# keyBoard_B.net
KiCad netlist of a schematic drawn in EAGLE
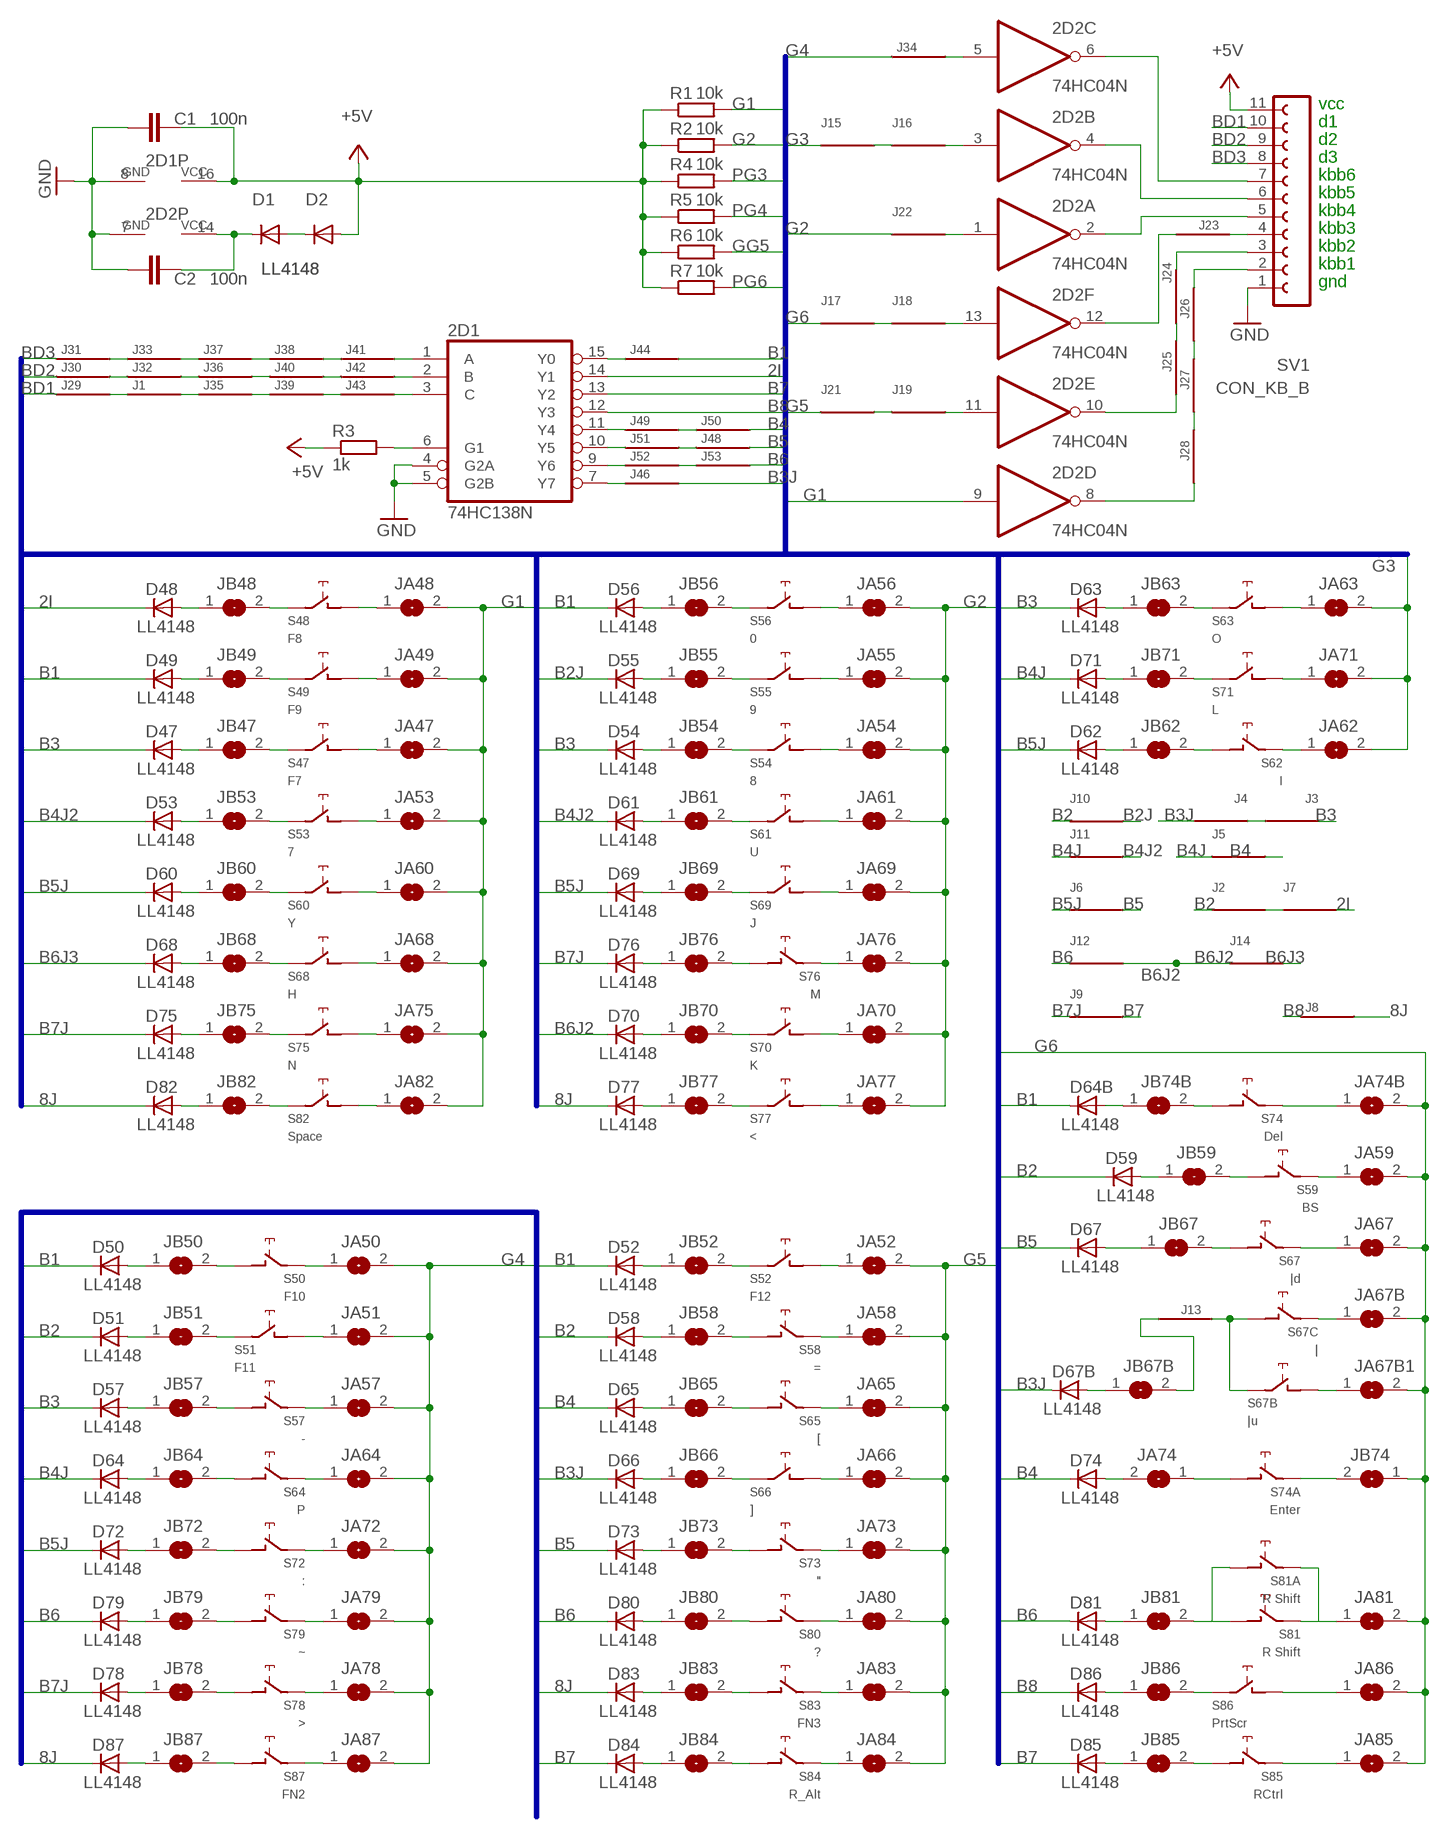
[diagram p0: schematic, sheet 1]

(export (version "E")
  (design (tool "Eeschema 10.0.6"))
  (components
    (comp (ref "2D1")
      (value "74HC138N")
      (footprint "eagle-import:DIL16")
      (libsource (lib "eagle-import") (part "74138NAC"))
    )
    (comp (ref "2D2")
      (value "74HC04N")
      (footprint "eagle-import:DIL14")
      (libsource (lib "eagle-import") (part "7404NALS"))
    )
    (comp (ref "C1")
      (value "100n")
      (footprint "eagle-import:C0805")
      (libsource (lib "eagle-import") (part "C-EUC0805"))
    )
    (comp (ref "C2")
      (value "100n")
      (footprint "eagle-import:C1206")
      (libsource (lib "eagle-import") (part "C-EUC1206"))
    )
    (comp (ref "D1")
      (value "LL4148")
      (footprint "eagle-import:SOD80C")
      (libsource (lib "eagle-import") (part "LL4148"))
    )
    (comp (ref "D2")
      (value "LL4148")
      (footprint "eagle-import:SOD80C")
      (libsource (lib "eagle-import") (part "LL4148"))
    )
    (comp (ref "D47")
      (value "LL4148")
      (footprint "eagle-import:SOD80C")
      (libsource (lib "eagle-import") (part "LL4148"))
    )
    (comp (ref "D48")
      (value "LL4148")
      (footprint "eagle-import:SOD80C")
      (libsource (lib "eagle-import") (part "LL4148"))
    )
    (comp (ref "D49")
      (value "LL4148")
      (footprint "eagle-import:SOD80C")
      (libsource (lib "eagle-import") (part "LL4148"))
    )
    (comp (ref "D50")
      (value "LL4148")
      (footprint "eagle-import:SOD80C")
      (libsource (lib "eagle-import") (part "LL4148"))
    )
    (comp (ref "D51")
      (value "LL4148")
      (footprint "eagle-import:SOD80C")
      (libsource (lib "eagle-import") (part "LL4148"))
    )
    (comp (ref "D52")
      (value "LL4148")
      (footprint "eagle-import:SOD80C")
      (libsource (lib "eagle-import") (part "LL4148"))
    )
    (comp (ref "D53")
      (value "LL4148")
      (footprint "eagle-import:SOD80C")
      (libsource (lib "eagle-import") (part "LL4148"))
    )
    (comp (ref "D54")
      (value "LL4148")
      (footprint "eagle-import:SOD80C")
      (libsource (lib "eagle-import") (part "LL4148"))
    )
    (comp (ref "D55")
      (value "LL4148")
      (footprint "eagle-import:SOD80C")
      (libsource (lib "eagle-import") (part "LL4148"))
    )
    (comp (ref "D56")
      (value "LL4148")
      (footprint "eagle-import:SOD80C")
      (libsource (lib "eagle-import") (part "LL4148"))
    )
    (comp (ref "D57")
      (value "LL4148")
      (footprint "eagle-import:SOD80C")
      (libsource (lib "eagle-import") (part "LL4148"))
    )
    (comp (ref "D58")
      (value "LL4148")
      (footprint "eagle-import:SOD80C")
      (libsource (lib "eagle-import") (part "LL4148"))
    )
    (comp (ref "D59")
      (value "LL4148")
      (footprint "eagle-import:SOD80C")
      (libsource (lib "eagle-import") (part "LL4148"))
    )
    (comp (ref "D60")
      (value "LL4148")
      (footprint "eagle-import:SOD80C")
      (libsource (lib "eagle-import") (part "LL4148"))
    )
    (comp (ref "D61")
      (value "LL4148")
      (footprint "eagle-import:SOD80C")
      (libsource (lib "eagle-import") (part "LL4148"))
    )
    (comp (ref "D62")
      (value "LL4148")
      (footprint "eagle-import:SOD80C")
      (libsource (lib "eagle-import") (part "LL4148"))
    )
    (comp (ref "D63")
      (value "LL4148")
      (footprint "eagle-import:SOD80C")
      (libsource (lib "eagle-import") (part "LL4148"))
    )
    (comp (ref "D64")
      (value "LL4148")
      (footprint "eagle-import:SOD80C")
      (libsource (lib "eagle-import") (part "LL4148"))
    )
    (comp (ref "D64B")
      (value "LL4148")
      (footprint "eagle-import:SOD80C")
      (libsource (lib "eagle-import") (part "LL4148"))
    )
    (comp (ref "D65")
      (value "LL4148")
      (footprint "eagle-import:SOD80C")
      (libsource (lib "eagle-import") (part "LL4148"))
    )
    (comp (ref "D66")
      (value "LL4148")
      (footprint "eagle-import:SOD80C")
      (libsource (lib "eagle-import") (part "LL4148"))
    )
    (comp (ref "D67")
      (value "LL4148")
      (footprint "eagle-import:SOD80C")
      (libsource (lib "eagle-import") (part "LL4148"))
    )
    (comp (ref "D67B")
      (value "LL4148")
      (footprint "eagle-import:SOD80C")
      (libsource (lib "eagle-import") (part "LL4148"))
    )
    (comp (ref "D68")
      (value "LL4148")
      (footprint "eagle-import:SOD80C")
      (libsource (lib "eagle-import") (part "LL4148"))
    )
    (comp (ref "D69")
      (value "LL4148")
      (footprint "eagle-import:SOD80C")
      (libsource (lib "eagle-import") (part "LL4148"))
    )
    (comp (ref "D70")
      (value "LL4148")
      (footprint "eagle-import:SOD80C")
      (libsource (lib "eagle-import") (part "LL4148"))
    )
    (comp (ref "D71")
      (value "LL4148")
      (footprint "eagle-import:SOD80C")
      (libsource (lib "eagle-import") (part "LL4148"))
    )
    (comp (ref "D72")
      (value "LL4148")
      (footprint "eagle-import:SOD80C")
      (libsource (lib "eagle-import") (part "LL4148"))
    )
    (comp (ref "D73")
      (value "LL4148")
      (footprint "eagle-import:SOD80C")
      (libsource (lib "eagle-import") (part "LL4148"))
    )
    (comp (ref "D74")
      (value "LL4148")
      (footprint "eagle-import:SOD80C")
      (libsource (lib "eagle-import") (part "LL4148"))
    )
    (comp (ref "D75")
      (value "LL4148")
      (footprint "eagle-import:SOD80C")
      (libsource (lib "eagle-import") (part "LL4148"))
    )
    (comp (ref "D76")
      (value "LL4148")
      (footprint "eagle-import:SOD80C")
      (libsource (lib "eagle-import") (part "LL4148"))
    )
    (comp (ref "D77")
      (value "LL4148")
      (footprint "eagle-import:SOD80C")
      (libsource (lib "eagle-import") (part "LL4148"))
    )
    (comp (ref "D78")
      (value "LL4148")
      (footprint "eagle-import:SOD80C")
      (libsource (lib "eagle-import") (part "LL4148"))
    )
    (comp (ref "D79")
      (value "LL4148")
      (footprint "eagle-import:SOD80C")
      (libsource (lib "eagle-import") (part "LL4148"))
    )
    (comp (ref "D80")
      (value "LL4148")
      (footprint "eagle-import:SOD80C")
      (libsource (lib "eagle-import") (part "LL4148"))
    )
    (comp (ref "D81")
      (value "LL4148")
      (footprint "eagle-import:SOD80C")
      (libsource (lib "eagle-import") (part "LL4148"))
    )
    (comp (ref "D82")
      (value "LL4148")
      (footprint "eagle-import:SOD80C")
      (libsource (lib "eagle-import") (part "LL4148"))
    )
    (comp (ref "D83")
      (value "LL4148")
      (footprint "eagle-import:SOD80C")
      (libsource (lib "eagle-import") (part "LL4148"))
    )
    (comp (ref "D84")
      (value "LL4148")
      (footprint "eagle-import:SOD80C")
      (libsource (lib "eagle-import") (part "LL4148"))
    )
    (comp (ref "D85")
      (value "LL4148")
      (footprint "eagle-import:SOD80C")
      (libsource (lib "eagle-import") (part "LL4148"))
    )
    (comp (ref "D86")
      (value "LL4148")
      (footprint "eagle-import:SOD80C")
      (libsource (lib "eagle-import") (part "LL4148"))
    )
    (comp (ref "D87")
      (value "LL4148")
      (footprint "eagle-import:SOD80C")
      (libsource (lib "eagle-import") (part "LL4148"))
    )
    (comp (ref "J1")
      (value "J")
      (footprint "eagle-import:R1206W")
      (libsource (lib "eagle-import") (part "J"))
    )
    (comp (ref "J2")
      (value "J")
      (footprint "eagle-import:R1206W")
      (libsource (lib "eagle-import") (part "J"))
    )
    (comp (ref "J3")
      (value "J")
      (footprint "eagle-import:R1206W")
      (libsource (lib "eagle-import") (part "J"))
    )
    (comp (ref "J4")
      (value "J")
      (footprint "eagle-import:R1206W")
      (libsource (lib "eagle-import") (part "J"))
    )
    (comp (ref "J5")
      (value "J")
      (footprint "eagle-import:R1206W")
      (libsource (lib "eagle-import") (part "J"))
    )
    (comp (ref "J6")
      (value "J")
      (footprint "eagle-import:R1206W")
      (libsource (lib "eagle-import") (part "J"))
    )
    (comp (ref "J7")
      (value "J")
      (footprint "eagle-import:R1206W")
      (libsource (lib "eagle-import") (part "J"))
    )
    (comp (ref "J8")
      (value "J")
      (footprint "eagle-import:R1206W")
      (libsource (lib "eagle-import") (part "J"))
    )
    (comp (ref "J9")
      (value "J")
      (footprint "eagle-import:R1206W")
      (libsource (lib "eagle-import") (part "J"))
    )
    (comp (ref "J10")
      (value "J")
      (footprint "eagle-import:R1206W")
      (libsource (lib "eagle-import") (part "J"))
    )
    (comp (ref "J11")
      (value "J")
      (footprint "eagle-import:R1206W")
      (libsource (lib "eagle-import") (part "J"))
    )
    (comp (ref "J12")
      (value "J")
      (footprint "eagle-import:R1206W")
      (libsource (lib "eagle-import") (part "J"))
    )
    (comp (ref "J13")
      (value "J")
      (footprint "eagle-import:R1206W")
      (libsource (lib "eagle-import") (part "J"))
    )
    (comp (ref "J14")
      (value "J")
      (footprint "eagle-import:R1206W")
      (libsource (lib "eagle-import") (part "J"))
    )
    (comp (ref "J15")
      (value "J")
      (footprint "eagle-import:R1206W")
      (libsource (lib "eagle-import") (part "J"))
    )
    (comp (ref "J16")
      (value "J")
      (footprint "eagle-import:R1206W")
      (libsource (lib "eagle-import") (part "J"))
    )
    (comp (ref "J17")
      (value "J")
      (footprint "eagle-import:R1206W")
      (libsource (lib "eagle-import") (part "J"))
    )
    (comp (ref "J18")
      (value "J")
      (footprint "eagle-import:R1206W")
      (libsource (lib "eagle-import") (part "J"))
    )
    (comp (ref "J19")
      (value "J")
      (footprint "eagle-import:R1206W")
      (libsource (lib "eagle-import") (part "J"))
    )
    (comp (ref "J21")
      (value "J")
      (footprint "eagle-import:R1206W")
      (libsource (lib "eagle-import") (part "J"))
    )
    (comp (ref "J22")
      (value "J")
      (footprint "eagle-import:R1206W")
      (libsource (lib "eagle-import") (part "J"))
    )
    (comp (ref "J23")
      (value "J")
      (footprint "eagle-import:R1206W")
      (libsource (lib "eagle-import") (part "J"))
    )
    (comp (ref "J24")
      (value "J")
      (footprint "eagle-import:R1206W")
      (libsource (lib "eagle-import") (part "J"))
    )
    (comp (ref "J25")
      (value "J")
      (footprint "eagle-import:R1206W")
      (libsource (lib "eagle-import") (part "J"))
    )
    (comp (ref "J26")
      (value "J")
      (footprint "eagle-import:R1206W")
      (libsource (lib "eagle-import") (part "J"))
    )
    (comp (ref "J27")
      (value "J")
      (footprint "eagle-import:R1206W")
      (libsource (lib "eagle-import") (part "J"))
    )
    (comp (ref "J28")
      (value "J")
      (footprint "eagle-import:R1206W")
      (libsource (lib "eagle-import") (part "J"))
    )
    (comp (ref "J29")
      (value "J")
      (footprint "eagle-import:R1206W")
      (libsource (lib "eagle-import") (part "J"))
    )
    (comp (ref "J30")
      (value "J")
      (footprint "eagle-import:R1206W")
      (libsource (lib "eagle-import") (part "J"))
    )
    (comp (ref "J31")
      (value "J")
      (footprint "eagle-import:R1206W")
      (libsource (lib "eagle-import") (part "J"))
    )
    (comp (ref "J32")
      (value "J")
      (footprint "eagle-import:R1206W")
      (libsource (lib "eagle-import") (part "J"))
    )
    (comp (ref "J33")
      (value "J")
      (footprint "eagle-import:R1206W")
      (libsource (lib "eagle-import") (part "J"))
    )
    (comp (ref "J34")
      (value "J")
      (footprint "eagle-import:R1206W")
      (libsource (lib "eagle-import") (part "J"))
    )
    (comp (ref "J35")
      (value "J")
      (footprint "eagle-import:R1206W")
      (libsource (lib "eagle-import") (part "J"))
    )
    (comp (ref "J36")
      (value "J")
      (footprint "eagle-import:R1206W")
      (libsource (lib "eagle-import") (part "J"))
    )
    (comp (ref "J37")
      (value "J")
      (footprint "eagle-import:R1206W")
      (libsource (lib "eagle-import") (part "J"))
    )
    (comp (ref "J38")
      (value "J")
      (footprint "eagle-import:R1206W")
      (libsource (lib "eagle-import") (part "J"))
    )
    (comp (ref "J39")
      (value "J")
      (footprint "eagle-import:R1206W")
      (libsource (lib "eagle-import") (part "J"))
    )
    (comp (ref "J40")
      (value "J")
      (footprint "eagle-import:R1206W")
      (libsource (lib "eagle-import") (part "J"))
    )
    (comp (ref "J41")
      (value "J")
      (footprint "eagle-import:R1206W")
      (libsource (lib "eagle-import") (part "J"))
    )
    (comp (ref "J42")
      (value "J")
      (footprint "eagle-import:R1206W")
      (libsource (lib "eagle-import") (part "J"))
    )
    (comp (ref "J43")
      (value "J")
      (footprint "eagle-import:R1206W")
      (libsource (lib "eagle-import") (part "J"))
    )
    (comp (ref "J44")
      (value "J")
      (footprint "eagle-import:R1206W")
      (libsource (lib "eagle-import") (part "J"))
    )
    (comp (ref "J46")
      (value "J")
      (footprint "eagle-import:R1206W")
      (libsource (lib "eagle-import") (part "J"))
    )
    (comp (ref "J48")
      (value "J")
      (footprint "eagle-import:R1206W")
      (libsource (lib "eagle-import") (part "J"))
    )
    (comp (ref "J49")
      (value "J")
      (footprint "eagle-import:R1206W")
      (libsource (lib "eagle-import") (part "J"))
    )
    (comp (ref "J50")
      (value "J")
      (footprint "eagle-import:R1206W")
      (libsource (lib "eagle-import") (part "J"))
    )
    (comp (ref "J51")
      (value "J")
      (footprint "eagle-import:R1206W")
      (libsource (lib "eagle-import") (part "J"))
    )
    (comp (ref "J52")
      (value "J")
      (footprint "eagle-import:R1206W")
      (libsource (lib "eagle-import") (part "J"))
    )
    (comp (ref "J53")
      (value "J")
      (footprint "eagle-import:R1206W")
      (libsource (lib "eagle-import") (part "J"))
    )
    (comp (ref "JA47")
      (value "SJ")
      (footprint "eagle-import:SJ")
      (libsource (lib "eagle-import") (part "SJ"))
    )
    (comp (ref "JA48")
      (value "SJ")
      (footprint "eagle-import:SJ")
      (libsource (lib "eagle-import") (part "SJ"))
    )
    (comp (ref "JA49")
      (value "SJ")
      (footprint "eagle-import:SJ")
      (libsource (lib "eagle-import") (part "SJ"))
    )
    (comp (ref "JA50")
      (value "SJ")
      (footprint "eagle-import:SJ")
      (libsource (lib "eagle-import") (part "SJ"))
    )
    (comp (ref "JA51")
      (value "SJ")
      (footprint "eagle-import:SJ")
      (libsource (lib "eagle-import") (part "SJ"))
    )
    (comp (ref "JA52")
      (value "SJ")
      (footprint "eagle-import:SJ")
      (libsource (lib "eagle-import") (part "SJ"))
    )
    (comp (ref "JA53")
      (value "SJ")
      (footprint "eagle-import:SJ")
      (libsource (lib "eagle-import") (part "SJ"))
    )
    (comp (ref "JA54")
      (value "SJ")
      (footprint "eagle-import:SJ")
      (libsource (lib "eagle-import") (part "SJ"))
    )
    (comp (ref "JA55")
      (value "SJ")
      (footprint "eagle-import:SJ")
      (libsource (lib "eagle-import") (part "SJ"))
    )
    (comp (ref "JA56")
      (value "SJ")
      (footprint "eagle-import:SJ")
      (libsource (lib "eagle-import") (part "SJ"))
    )
    (comp (ref "JA57")
      (value "SJ")
      (footprint "eagle-import:SJ")
      (libsource (lib "eagle-import") (part "SJ"))
    )
    (comp (ref "JA58")
      (value "SJ")
      (footprint "eagle-import:SJ")
      (libsource (lib "eagle-import") (part "SJ"))
    )
    (comp (ref "JA59")
      (value "SJ")
      (footprint "eagle-import:SJ")
      (libsource (lib "eagle-import") (part "SJ"))
    )
    (comp (ref "JA60")
      (value "SJ")
      (footprint "eagle-import:SJ")
      (libsource (lib "eagle-import") (part "SJ"))
    )
    (comp (ref "JA61")
      (value "SJ")
      (footprint "eagle-import:SJ")
      (libsource (lib "eagle-import") (part "SJ"))
    )
    (comp (ref "JA62")
      (value "SJ")
      (footprint "eagle-import:SJ")
      (libsource (lib "eagle-import") (part "SJ"))
    )
    (comp (ref "JA63")
      (value "SJ")
      (footprint "eagle-import:SJ")
      (libsource (lib "eagle-import") (part "SJ"))
    )
    (comp (ref "JA64")
      (value "SJ")
      (footprint "eagle-import:SJ")
      (libsource (lib "eagle-import") (part "SJ"))
    )
    (comp (ref "JA65")
      (value "SJ")
      (footprint "eagle-import:SJ")
      (libsource (lib "eagle-import") (part "SJ"))
    )
    (comp (ref "JA66")
      (value "SJ")
      (footprint "eagle-import:SJ")
      (libsource (lib "eagle-import") (part "SJ"))
    )
    (comp (ref "JA67")
      (value "SJ")
      (footprint "eagle-import:SJ")
      (libsource (lib "eagle-import") (part "SJ"))
    )
    (comp (ref "JA67B")
      (value "SJ")
      (footprint "eagle-import:SJ")
      (libsource (lib "eagle-import") (part "SJ"))
    )
    (comp (ref "JA67B1")
      (value "SJ")
      (footprint "eagle-import:SJ")
      (libsource (lib "eagle-import") (part "SJ"))
    )
    (comp (ref "JA68")
      (value "SJ")
      (footprint "eagle-import:SJ")
      (libsource (lib "eagle-import") (part "SJ"))
    )
    (comp (ref "JA69")
      (value "SJ")
      (footprint "eagle-import:SJ")
      (libsource (lib "eagle-import") (part "SJ"))
    )
    (comp (ref "JA70")
      (value "SJ")
      (footprint "eagle-import:SJ")
      (libsource (lib "eagle-import") (part "SJ"))
    )
    (comp (ref "JA71")
      (value "SJ")
      (footprint "eagle-import:SJ")
      (libsource (lib "eagle-import") (part "SJ"))
    )
    (comp (ref "JA72")
      (value "SJ")
      (footprint "eagle-import:SJ")
      (libsource (lib "eagle-import") (part "SJ"))
    )
    (comp (ref "JA73")
      (value "SJ")
      (footprint "eagle-import:SJ")
      (libsource (lib "eagle-import") (part "SJ"))
    )
    (comp (ref "JA74")
      (value "SJ")
      (footprint "eagle-import:SJ")
      (libsource (lib "eagle-import") (part "SJ"))
    )
    (comp (ref "JA74B")
      (value "SJ")
      (footprint "eagle-import:SJ")
      (libsource (lib "eagle-import") (part "SJ"))
    )
    (comp (ref "JA75")
      (value "SJ")
      (footprint "eagle-import:SJ")
      (libsource (lib "eagle-import") (part "SJ"))
    )
    (comp (ref "JA76")
      (value "SJ")
      (footprint "eagle-import:SJ")
      (libsource (lib "eagle-import") (part "SJ"))
    )
    (comp (ref "JA77")
      (value "SJ")
      (footprint "eagle-import:SJ")
      (libsource (lib "eagle-import") (part "SJ"))
    )
    (comp (ref "JA78")
      (value "SJ")
      (footprint "eagle-import:SJ")
      (libsource (lib "eagle-import") (part "SJ"))
    )
    (comp (ref "JA79")
      (value "SJ")
      (footprint "eagle-import:SJ")
      (libsource (lib "eagle-import") (part "SJ"))
    )
    (comp (ref "JA80")
      (value "SJ")
      (footprint "eagle-import:SJ")
      (libsource (lib "eagle-import") (part "SJ"))
    )
    (comp (ref "JA81")
      (value "SJ")
      (footprint "eagle-import:SJ")
      (libsource (lib "eagle-import") (part "SJ"))
    )
    (comp (ref "JA82")
      (value "SJ")
      (footprint "eagle-import:SJ")
      (libsource (lib "eagle-import") (part "SJ"))
    )
    (comp (ref "JA83")
      (value "SJ")
      (footprint "eagle-import:SJ")
      (libsource (lib "eagle-import") (part "SJ"))
    )
    (comp (ref "JA84")
      (value "SJ")
      (footprint "eagle-import:SJ")
      (libsource (lib "eagle-import") (part "SJ"))
    )
    (comp (ref "JA85")
      (value "SJ")
      (footprint "eagle-import:SJ")
      (libsource (lib "eagle-import") (part "SJ"))
    )
    (comp (ref "JA86")
      (value "SJ")
      (footprint "eagle-import:SJ")
      (libsource (lib "eagle-import") (part "SJ"))
    )
    (comp (ref "JA87")
      (value "SJ")
      (footprint "eagle-import:SJ")
      (libsource (lib "eagle-import") (part "SJ"))
    )
    (comp (ref "JB47")
      (value "SJ")
      (footprint "eagle-import:SJ")
      (libsource (lib "eagle-import") (part "SJ"))
    )
    (comp (ref "JB48")
      (value "SJ")
      (footprint "eagle-import:SJ")
      (libsource (lib "eagle-import") (part "SJ"))
    )
    (comp (ref "JB49")
      (value "SJ")
      (footprint "eagle-import:SJ")
      (libsource (lib "eagle-import") (part "SJ"))
    )
    (comp (ref "JB50")
      (value "SJ")
      (footprint "eagle-import:SJ")
      (libsource (lib "eagle-import") (part "SJ"))
    )
    (comp (ref "JB51")
      (value "SJ")
      (footprint "eagle-import:SJ")
      (libsource (lib "eagle-import") (part "SJ"))
    )
    (comp (ref "JB52")
      (value "SJ")
      (footprint "eagle-import:SJ")
      (libsource (lib "eagle-import") (part "SJ"))
    )
    (comp (ref "JB53")
      (value "SJ")
      (footprint "eagle-import:SJ")
      (libsource (lib "eagle-import") (part "SJ"))
    )
    (comp (ref "JB54")
      (value "SJ")
      (footprint "eagle-import:SJ")
      (libsource (lib "eagle-import") (part "SJ"))
    )
    (comp (ref "JB55")
      (value "SJ")
      (footprint "eagle-import:SJ")
      (libsource (lib "eagle-import") (part "SJ"))
    )
    (comp (ref "JB56")
      (value "SJ")
      (footprint "eagle-import:SJ")
      (libsource (lib "eagle-import") (part "SJ"))
    )
    (comp (ref "JB57")
      (value "SJ")
      (footprint "eagle-import:SJ")
      (libsource (lib "eagle-import") (part "SJ"))
    )
    (comp (ref "JB58")
      (value "SJ")
      (footprint "eagle-import:SJ")
      (libsource (lib "eagle-import") (part "SJ"))
    )
    (comp (ref "JB59")
      (value "SJ")
      (footprint "eagle-import:SJ")
      (libsource (lib "eagle-import") (part "SJ"))
    )
    (comp (ref "JB60")
      (value "SJ")
      (footprint "eagle-import:SJ")
      (libsource (lib "eagle-import") (part "SJ"))
    )
    (comp (ref "JB61")
      (value "SJ")
      (footprint "eagle-import:SJ")
      (libsource (lib "eagle-import") (part "SJ"))
    )
    (comp (ref "JB62")
      (value "SJ")
      (footprint "eagle-import:SJ")
      (libsource (lib "eagle-import") (part "SJ"))
    )
    (comp (ref "JB63")
      (value "SJ")
      (footprint "eagle-import:SJ")
      (libsource (lib "eagle-import") (part "SJ"))
    )
    (comp (ref "JB64")
      (value "SJ")
      (footprint "eagle-import:SJ")
      (libsource (lib "eagle-import") (part "SJ"))
    )
    (comp (ref "JB65")
      (value "SJ")
      (footprint "eagle-import:SJ")
      (libsource (lib "eagle-import") (part "SJ"))
    )
    (comp (ref "JB66")
      (value "SJ")
      (footprint "eagle-import:SJ")
      (libsource (lib "eagle-import") (part "SJ"))
    )
    (comp (ref "JB67")
      (value "SJ")
      (footprint "eagle-import:SJ")
      (libsource (lib "eagle-import") (part "SJ"))
    )
    (comp (ref "JB67B")
      (value "SJ")
      (footprint "eagle-import:SJ")
      (libsource (lib "eagle-import") (part "SJ"))
    )
    (comp (ref "JB68")
      (value "SJ")
      (footprint "eagle-import:SJ")
      (libsource (lib "eagle-import") (part "SJ"))
    )
    (comp (ref "JB69")
      (value "SJ")
      (footprint "eagle-import:SJ")
      (libsource (lib "eagle-import") (part "SJ"))
    )
    (comp (ref "JB70")
      (value "SJ")
      (footprint "eagle-import:SJ")
      (libsource (lib "eagle-import") (part "SJ"))
    )
    (comp (ref "JB71")
      (value "SJ")
      (footprint "eagle-import:SJ")
      (libsource (lib "eagle-import") (part "SJ"))
    )
    (comp (ref "JB72")
      (value "SJ")
      (footprint "eagle-import:SJ")
      (libsource (lib "eagle-import") (part "SJ"))
    )
    (comp (ref "JB73")
      (value "SJ")
      (footprint "eagle-import:SJ")
      (libsource (lib "eagle-import") (part "SJ"))
    )
    (comp (ref "JB74")
      (value "SJ")
      (footprint "eagle-import:SJ")
      (libsource (lib "eagle-import") (part "SJ"))
    )
    (comp (ref "JB74B")
      (value "SJ")
      (footprint "eagle-import:SJ")
      (libsource (lib "eagle-import") (part "SJ"))
    )
    (comp (ref "JB75")
      (value "SJ")
      (footprint "eagle-import:SJ")
      (libsource (lib "eagle-import") (part "SJ"))
    )
    (comp (ref "JB76")
      (value "SJ")
      (footprint "eagle-import:SJ")
      (libsource (lib "eagle-import") (part "SJ"))
    )
    (comp (ref "JB77")
      (value "SJ")
      (footprint "eagle-import:SJ")
      (libsource (lib "eagle-import") (part "SJ"))
    )
    (comp (ref "JB78")
      (value "SJ")
      (footprint "eagle-import:SJ")
      (libsource (lib "eagle-import") (part "SJ"))
    )
    (comp (ref "JB79")
      (value "SJ")
      (footprint "eagle-import:SJ")
      (libsource (lib "eagle-import") (part "SJ"))
    )
    (comp (ref "JB80")
      (value "SJ")
      (footprint "eagle-import:SJ")
      (libsource (lib "eagle-import") (part "SJ"))
    )
    (comp (ref "JB81")
      (value "SJ")
      (footprint "eagle-import:SJ")
      (libsource (lib "eagle-import") (part "SJ"))
    )
    (comp (ref "JB82")
      (value "SJ")
      (footprint "eagle-import:SJ")
      (libsource (lib "eagle-import") (part "SJ"))
    )
    (comp (ref "JB83")
      (value "SJ")
      (footprint "eagle-import:SJ")
      (libsource (lib "eagle-import") (part "SJ"))
    )
    (comp (ref "JB84")
      (value "SJ")
      (footprint "eagle-import:SJ")
      (libsource (lib "eagle-import") (part "SJ"))
    )
    (comp (ref "JB85")
      (value "SJ")
      (footprint "eagle-import:SJ")
      (libsource (lib "eagle-import") (part "SJ"))
    )
    (comp (ref "JB86")
      (value "SJ")
      (footprint "eagle-import:SJ")
      (libsource (lib "eagle-import") (part "SJ"))
    )
    (comp (ref "JB87")
      (value "SJ")
      (footprint "eagle-import:SJ")
      (libsource (lib "eagle-import") (part "SJ"))
    )
    (comp (ref "R1")
      (value "10k")
      (footprint "eagle-import:R0805")
      (libsource (lib "eagle-import") (part "R-EU_R0805"))
    )
    (comp (ref "R2")
      (value "10k")
      (footprint "eagle-import:R0805")
      (libsource (lib "eagle-import") (part "R-EU_R0805"))
    )
    (comp (ref "R3")
      (value "1k")
      (footprint "eagle-import:R0805")
      (libsource (lib "eagle-import") (part "R-EU_R0805"))
    )
    (comp (ref "R4")
      (value "10k")
      (footprint "eagle-import:R0805")
      (libsource (lib "eagle-import") (part "R-EU_R0805"))
    )
    (comp (ref "R5")
      (value "10k")
      (footprint "eagle-import:R1206W")
      (libsource (lib "eagle-import") (part "R-EU_R1206W"))
    )
    (comp (ref "R6")
      (value "10k")
      (footprint "eagle-import:R0805")
      (libsource (lib "eagle-import") (part "R-EU_R0805"))
    )
    (comp (ref "R7")
      (value "10k")
      (footprint "eagle-import:R0805")
      (libsource (lib "eagle-import") (part "R-EU_R0805"))
    )
    (comp (ref "S47")
      (value "F7")
      (footprint "eagle-import:CHERRY-MX-4P")
      (libsource (lib "eagle-import") (part "CHERRY-MX-4P"))
    )
    (comp (ref "S48")
      (value "F8")
      (footprint "eagle-import:CHERRY-MX-4P")
      (libsource (lib "eagle-import") (part "CHERRY-MX-4P"))
    )
    (comp (ref "S49")
      (value "F9")
      (footprint "eagle-import:CHERRY-MX-4P")
      (libsource (lib "eagle-import") (part "CHERRY-MX-4P"))
    )
    (comp (ref "S50")
      (value "F10")
      (footprint "eagle-import:CHERRY-MX-4P")
      (libsource (lib "eagle-import") (part "CHERRY-MX-4P"))
    )
    (comp (ref "S51")
      (value "F11")
      (footprint "eagle-import:CHERRY-MX-4P")
      (libsource (lib "eagle-import") (part "CHERRY-MX-4P"))
    )
    (comp (ref "S52")
      (value "F12")
      (footprint "eagle-import:CHERRY-MX-4P")
      (libsource (lib "eagle-import") (part "CHERRY-MX-4P"))
    )
    (comp (ref "S53")
      (value "7")
      (footprint "eagle-import:CHERRY-MX-4P")
      (libsource (lib "eagle-import") (part "CHERRY-MX-4P"))
    )
    (comp (ref "S54")
      (value "8")
      (footprint "eagle-import:CHERRY-MX-4P")
      (libsource (lib "eagle-import") (part "CHERRY-MX-4P"))
    )
    (comp (ref "S55")
      (value "9")
      (footprint "eagle-import:CHERRY-MX-4P")
      (libsource (lib "eagle-import") (part "CHERRY-MX-4P"))
    )
    (comp (ref "S56")
      (value "0")
      (footprint "eagle-import:CHERRY-MX-4P")
      (libsource (lib "eagle-import") (part "CHERRY-MX-4P"))
    )
    (comp (ref "S57")
      (value "-")
      (footprint "eagle-import:CHERRY-MX-4P")
      (libsource (lib "eagle-import") (part "CHERRY-MX-4P"))
    )
    (comp (ref "S58")
      (value "=")
      (footprint "eagle-import:CHERRY-MX-4P")
      (libsource (lib "eagle-import") (part "CHERRY-MX-4P"))
    )
    (comp (ref "S59")
      (value "BS")
      (footprint "eagle-import:CHERRY-MX-4P")
      (libsource (lib "eagle-import") (part "CHERRY-MX-4P"))
    )
    (comp (ref "S60")
      (value "Y")
      (footprint "eagle-import:CHERRY-MX-4P")
      (libsource (lib "eagle-import") (part "CHERRY-MX-4P"))
    )
    (comp (ref "S61")
      (value "U")
      (footprint "eagle-import:CHERRY-MX-4P")
      (libsource (lib "eagle-import") (part "CHERRY-MX-4P"))
    )
    (comp (ref "S62")
      (value "I")
      (footprint "eagle-import:CHERRY-MX-4P")
      (libsource (lib "eagle-import") (part "CHERRY-MX-4P"))
    )
    (comp (ref "S63")
      (value "O")
      (footprint "eagle-import:CHERRY-MX-4P")
      (libsource (lib "eagle-import") (part "CHERRY-MX-4P"))
    )
    (comp (ref "S64")
      (value "P")
      (footprint "eagle-import:CHERRY-MX-4P")
      (libsource (lib "eagle-import") (part "CHERRY-MX-4P"))
    )
    (comp (ref "S65")
      (value "[")
      (footprint "eagle-import:CHERRY-MX-4P")
      (libsource (lib "eagle-import") (part "CHERRY-MX-4P"))
    )
    (comp (ref "S66")
      (value "]")
      (footprint "eagle-import:CHERRY-MX-4P")
      (libsource (lib "eagle-import") (part "CHERRY-MX-4P"))
    )
    (comp (ref "S67")
      (value "|d")
      (footprint "eagle-import:CHERRY-MX-4P")
      (libsource (lib "eagle-import") (part "CHERRY-MX-4P"))
    )
    (comp (ref "S67B")
      (value "|u")
      (footprint "eagle-import:CHERRY-MX")
      (libsource (lib "eagle-import") (part "CHERRY-MX"))
    )
    (comp (ref "S67C")
      (value "|")
      (footprint "eagle-import:CHERRY-MX-4P")
      (libsource (lib "eagle-import") (part "CHERRY-MX-4P"))
    )
    (comp (ref "S68")
      (value "H")
      (footprint "eagle-import:CHERRY-MX-4P")
      (libsource (lib "eagle-import") (part "CHERRY-MX-4P"))
    )
    (comp (ref "S69")
      (value "J")
      (footprint "eagle-import:CHERRY-MX-4P")
      (libsource (lib "eagle-import") (part "CHERRY-MX-4P"))
    )
    (comp (ref "S70")
      (value "K")
      (footprint "eagle-import:CHERRY-MX-4P")
      (libsource (lib "eagle-import") (part "CHERRY-MX-4P"))
    )
    (comp (ref "S71")
      (value "L")
      (footprint "eagle-import:CHERRY-MX-4P")
      (libsource (lib "eagle-import") (part "CHERRY-MX-4P"))
    )
    (comp (ref "S72")
      (value ":")
      (footprint "eagle-import:CHERRY-MX-4P")
      (libsource (lib "eagle-import") (part "CHERRY-MX-4P"))
    )
    (comp (ref "S73")
      (value "\"")
      (footprint "eagle-import:CHERRY-MX-4P")
      (libsource (lib "eagle-import") (part "CHERRY-MX-4P"))
    )
    (comp (ref "S74")
      (value "Del")
      (footprint "eagle-import:CHERRY-MX-4P")
      (libsource (lib "eagle-import") (part "CHERRY-MX-4P"))
    )
    (comp (ref "S74A")
      (value "Enter")
      (footprint "eagle-import:CHERRY-MX-4P")
      (libsource (lib "eagle-import") (part "CHERRY-MX-4P"))
    )
    (comp (ref "S75")
      (value "N")
      (footprint "eagle-import:CHERRY-MX-4P")
      (libsource (lib "eagle-import") (part "CHERRY-MX-4P"))
    )
    (comp (ref "S76")
      (value "M")
      (footprint "eagle-import:CHERRY-MX-4P")
      (libsource (lib "eagle-import") (part "CHERRY-MX-4P"))
    )
    (comp (ref "S77")
      (value "<")
      (footprint "eagle-import:CHERRY-MX-4P")
      (libsource (lib "eagle-import") (part "CHERRY-MX-4P"))
    )
    (comp (ref "S78")
      (value ">")
      (footprint "eagle-import:CHERRY-MX-4P")
      (libsource (lib "eagle-import") (part "CHERRY-MX-4P"))
    )
    (comp (ref "S79")
      (value "~")
      (footprint "eagle-import:CHERRY-MX-4P")
      (libsource (lib "eagle-import") (part "CHERRY-MX-4P"))
    )
    (comp (ref "S80")
      (value "?")
      (footprint "eagle-import:CHERRY-MX-4P")
      (libsource (lib "eagle-import") (part "CHERRY-MX-4P"))
    )
    (comp (ref "S81")
      (value "R Shift")
      (footprint "eagle-import:CHERRY-MX-4P")
      (libsource (lib "eagle-import") (part "CHERRY-MX-4P"))
    )
    (comp (ref "S81A")
      (value "R Shift")
      (footprint "eagle-import:CHERRY-MX-4P")
      (libsource (lib "eagle-import") (part "CHERRY-MX-4P"))
    )
    (comp (ref "S82")
      (value "Space")
      (footprint "eagle-import:CHERRY-MX-4P")
      (libsource (lib "eagle-import") (part "CHERRY-MX-4P"))
    )
    (comp (ref "S83")
      (value "FN3")
      (footprint "eagle-import:CHERRY-MX-4P")
      (libsource (lib "eagle-import") (part "CHERRY-MX-4P"))
    )
    (comp (ref "S84")
      (value "R_Alt")
      (footprint "eagle-import:CHERRY-MX-4P")
      (libsource (lib "eagle-import") (part "CHERRY-MX-4P"))
    )
    (comp (ref "S85")
      (value "RCtrl")
      (footprint "eagle-import:CHERRY-MX-4P")
      (libsource (lib "eagle-import") (part "CHERRY-MX-4P"))
    )
    (comp (ref "S86")
      (value "PrtScr")
      (footprint "eagle-import:CHERRY-MX-4P")
      (libsource (lib "eagle-import") (part "CHERRY-MX-4P"))
    )
    (comp (ref "S87")
      (value "FN2")
      (footprint "eagle-import:CHERRY-MX-4P")
      (libsource (lib "eagle-import") (part "CHERRY-MX-4P"))
    )
    (comp (ref "SV1")
      (value "CON_KB_B")
      (footprint "eagle-import:FE12")
      (libsource (lib "eagle-import") (part "FE12-1"))
    )
  )
  (nets
    (net (code "20") (name "+5V") (class "Default")
      (node (ref "2D1") (pin "16") (pinfunction "VCC_16") (pintype "power_in"))
      (node (ref "C1") (pin "1") (pinfunction "1_1") (pintype "passive"))
      (node (ref "D2") (pin "A") (pinfunction "A_A") (pintype "passive"))
      (node (ref "R1") (pin "1") (pinfunction "1_1") (pintype "passive"))
      (node (ref "R2") (pin "1") (pinfunction "1_1") (pintype "passive"))
      (node (ref "R3") (pin "1") (pinfunction "1_1") (pintype "passive"))
      (node (ref "R4") (pin "1") (pinfunction "1_1") (pintype "passive"))
      (node (ref "R5") (pin "1") (pinfunction "1_1") (pintype "passive"))
      (node (ref "R6") (pin "1") (pinfunction "1_1") (pintype "passive"))
      (node (ref "R7") (pin "1") (pinfunction "1_1") (pintype "passive"))
      (node (ref "SV1") (pin "11") (pinfunction "11_11") (pintype "passive"))
    )
    (net (code "21") (name "/2I") (class "Default")
      (node (ref "2D1") (pin "14") (pinfunction "Y1_14") (pintype "output"))
      (node (ref "D48") (pin "C") (pinfunction "C_C") (pintype "passive"))
      (node (ref "J7") (pin "1") (pinfunction "P$1_1") (pintype "bidirectional"))
    )
    (net (code "22") (name "/8J") (class "Default")
      (node (ref "D77") (pin "C") (pinfunction "C_C") (pintype "passive"))
      (node (ref "D82") (pin "C") (pinfunction "C_C") (pintype "passive"))
      (node (ref "D83") (pin "C") (pinfunction "C_C") (pintype "passive"))
      (node (ref "D87") (pin "C") (pinfunction "C_C") (pintype "passive"))
      (node (ref "J8") (pin "1") (pinfunction "P$1_1") (pintype "bidirectional"))
    )
    (net (code "23") (name "/B1") (class "Default")
      (node (ref "D49") (pin "C") (pinfunction "C_C") (pintype "passive"))
      (node (ref "D50") (pin "C") (pinfunction "C_C") (pintype "passive"))
      (node (ref "D52") (pin "C") (pinfunction "C_C") (pintype "passive"))
      (node (ref "D56") (pin "C") (pinfunction "C_C") (pintype "passive"))
      (node (ref "D64B") (pin "C") (pinfunction "C_C") (pintype "passive"))
      (node (ref "J44") (pin "1") (pinfunction "P$1_1") (pintype "bidirectional"))
    )
    (net (code "24") (name "/B2") (class "Default")
      (node (ref "D51") (pin "C") (pinfunction "C_C") (pintype "passive"))
      (node (ref "D58") (pin "C") (pinfunction "C_C") (pintype "passive"))
      (node (ref "D59") (pin "C") (pinfunction "C_C") (pintype "passive"))
      (node (ref "J10") (pin "2") (pinfunction "P$2_2") (pintype "bidirectional"))
      (node (ref "J2") (pin "2") (pinfunction "P$2_2") (pintype "bidirectional"))
    )
    (net (code "25") (name "/B2J") (class "Default")
      (node (ref "D55") (pin "C") (pinfunction "C_C") (pintype "passive"))
      (node (ref "J10") (pin "1") (pinfunction "P$1_1") (pintype "bidirectional"))
    )
    (net (code "26") (name "/B3") (class "Default")
      (node (ref "D47") (pin "C") (pinfunction "C_C") (pintype "passive"))
      (node (ref "D54") (pin "C") (pinfunction "C_C") (pintype "passive"))
      (node (ref "D57") (pin "C") (pinfunction "C_C") (pintype "passive"))
      (node (ref "D63") (pin "C") (pinfunction "C_C") (pintype "passive"))
      (node (ref "J3") (pin "2") (pinfunction "P$2_2") (pintype "bidirectional"))
    )
    (net (code "27") (name "/B3J") (class "Default")
      (node (ref "D66") (pin "C") (pinfunction "C_C") (pintype "passive"))
      (node (ref "D67B") (pin "C") (pinfunction "C_C") (pintype "passive"))
      (node (ref "J4") (pin "1") (pinfunction "P$1_1") (pintype "bidirectional"))
      (node (ref "J46") (pin "1") (pinfunction "P$1_1") (pintype "bidirectional"))
    )
    (net (code "28") (name "/B4") (class "Default")
      (node (ref "D65") (pin "C") (pinfunction "C_C") (pintype "passive"))
      (node (ref "D74") (pin "C") (pinfunction "C_C") (pintype "passive"))
      (node (ref "J5") (pin "1") (pinfunction "P$1_1") (pintype "bidirectional"))
      (node (ref "J50") (pin "1") (pinfunction "P$1_1") (pintype "bidirectional"))
    )
    (net (code "29") (name "/B4J") (class "Default")
      (node (ref "D64") (pin "C") (pinfunction "C_C") (pintype "passive"))
      (node (ref "D71") (pin "C") (pinfunction "C_C") (pintype "passive"))
      (node (ref "J11") (pin "2") (pinfunction "P$2_2") (pintype "bidirectional"))
      (node (ref "J5") (pin "2") (pinfunction "P$2_2") (pintype "bidirectional"))
    )
    (net (code "30") (name "/B4J2") (class "Default")
      (node (ref "D53") (pin "C") (pinfunction "C_C") (pintype "passive"))
      (node (ref "D61") (pin "C") (pinfunction "C_C") (pintype "passive"))
      (node (ref "J11") (pin "1") (pinfunction "P$1_1") (pintype "bidirectional"))
    )
    (net (code "31") (name "/B5") (class "Default")
      (node (ref "D67") (pin "C") (pinfunction "C_C") (pintype "passive"))
      (node (ref "D73") (pin "C") (pinfunction "C_C") (pintype "passive"))
      (node (ref "J48") (pin "1") (pinfunction "P$1_1") (pintype "bidirectional"))
      (node (ref "J6") (pin "1") (pinfunction "P$1_1") (pintype "bidirectional"))
    )
    (net (code "32") (name "/B5J") (class "Default")
      (node (ref "D60") (pin "C") (pinfunction "C_C") (pintype "passive"))
      (node (ref "D62") (pin "C") (pinfunction "C_C") (pintype "passive"))
      (node (ref "D69") (pin "C") (pinfunction "C_C") (pintype "passive"))
      (node (ref "D72") (pin "C") (pinfunction "C_C") (pintype "passive"))
      (node (ref "J6") (pin "2") (pinfunction "P$2_2") (pintype "bidirectional"))
    )
    (net (code "33") (name "/B6") (class "Default")
      (node (ref "D79") (pin "C") (pinfunction "C_C") (pintype "passive"))
      (node (ref "D80") (pin "C") (pinfunction "C_C") (pintype "passive"))
      (node (ref "D81") (pin "C") (pinfunction "C_C") (pintype "passive"))
      (node (ref "J12") (pin "2") (pinfunction "P$2_2") (pintype "bidirectional"))
      (node (ref "J53") (pin "1") (pinfunction "P$1_1") (pintype "bidirectional"))
    )
    (net (code "34") (name "/B6J2") (class "Default")
      (node (ref "D70") (pin "C") (pinfunction "C_C") (pintype "passive"))
      (node (ref "J12") (pin "1") (pinfunction "P$1_1") (pintype "bidirectional"))
      (node (ref "J14") (pin "2") (pinfunction "P$2_2") (pintype "bidirectional"))
    )
    (net (code "35") (name "/B6J3") (class "Default")
      (node (ref "D68") (pin "C") (pinfunction "C_C") (pintype "passive"))
      (node (ref "J14") (pin "1") (pinfunction "P$1_1") (pintype "bidirectional"))
    )
    (net (code "36") (name "/B7") (class "Default")
      (node (ref "2D1") (pin "13") (pinfunction "Y2_13") (pintype "output"))
      (node (ref "D84") (pin "C") (pinfunction "C_C") (pintype "passive"))
      (node (ref "D85") (pin "C") (pinfunction "C_C") (pintype "passive"))
      (node (ref "J9") (pin "1") (pinfunction "P$1_1") (pintype "bidirectional"))
    )
    (net (code "37") (name "/B7J") (class "Default")
      (node (ref "D75") (pin "C") (pinfunction "C_C") (pintype "passive"))
      (node (ref "D76") (pin "C") (pinfunction "C_C") (pintype "passive"))
      (node (ref "D78") (pin "C") (pinfunction "C_C") (pintype "passive"))
      (node (ref "J9") (pin "2") (pinfunction "P$2_2") (pintype "bidirectional"))
    )
    (net (code "38") (name "/B8") (class "Default")
      (node (ref "2D1") (pin "12") (pinfunction "Y3_12") (pintype "output"))
      (node (ref "D86") (pin "C") (pinfunction "C_C") (pintype "passive"))
      (node (ref "J8") (pin "2") (pinfunction "P$2_2") (pintype "bidirectional"))
    )
    (net (code "39") (name "/BD1") (class "Default")
      (node (ref "J29") (pin "2") (pinfunction "P$2_2") (pintype "bidirectional"))
      (node (ref "SV1") (pin "10") (pinfunction "10_10") (pintype "passive"))
    )
    (net (code "40") (name "/BD2") (class "Default")
      (node (ref "J30") (pin "2") (pinfunction "P$2_2") (pintype "bidirectional"))
      (node (ref "SV1") (pin "9") (pinfunction "9_9") (pintype "passive"))
    )
    (net (code "41") (name "/BD3") (class "Default")
      (node (ref "J31") (pin "2") (pinfunction "P$2_2") (pintype "bidirectional"))
      (node (ref "SV1") (pin "8") (pinfunction "8_8") (pintype "passive"))
    )
    (net (code "42") (name "/G1") (class "Default")
      (node (ref "2D2") (pin "9") (pinfunction "I_9") (pintype "input"))
      (node (ref "JA47") (pin "2") (pinfunction "2_2") (pintype "passive"))
      (node (ref "JA48") (pin "2") (pinfunction "2_2") (pintype "passive"))
      (node (ref "JA49") (pin "2") (pinfunction "2_2") (pintype "passive"))
      (node (ref "JA53") (pin "2") (pinfunction "2_2") (pintype "passive"))
      (node (ref "JA60") (pin "2") (pinfunction "2_2") (pintype "passive"))
      (node (ref "JA68") (pin "2") (pinfunction "2_2") (pintype "passive"))
      (node (ref "JA75") (pin "2") (pinfunction "2_2") (pintype "passive"))
      (node (ref "JA82") (pin "2") (pinfunction "2_2") (pintype "passive"))
      (node (ref "R1") (pin "2") (pinfunction "2_2") (pintype "passive"))
    )
    (net (code "43") (name "/G2") (class "Default")
      (node (ref "J22") (pin "2") (pinfunction "P$2_2") (pintype "bidirectional"))
      (node (ref "JA54") (pin "2") (pinfunction "2_2") (pintype "passive"))
      (node (ref "JA55") (pin "2") (pinfunction "2_2") (pintype "passive"))
      (node (ref "JA56") (pin "2") (pinfunction "2_2") (pintype "passive"))
      (node (ref "JA61") (pin "2") (pinfunction "2_2") (pintype "passive"))
      (node (ref "JA69") (pin "2") (pinfunction "2_2") (pintype "passive"))
      (node (ref "JA70") (pin "2") (pinfunction "2_2") (pintype "passive"))
      (node (ref "JA76") (pin "2") (pinfunction "2_2") (pintype "passive"))
      (node (ref "JA77") (pin "2") (pinfunction "2_2") (pintype "passive"))
      (node (ref "R2") (pin "2") (pinfunction "2_2") (pintype "passive"))
    )
    (net (code "44") (name "/G3") (class "Default")
      (node (ref "J15") (pin "2") (pinfunction "P$2_2") (pintype "bidirectional"))
      (node (ref "JA62") (pin "2") (pinfunction "2_2") (pintype "passive"))
      (node (ref "JA63") (pin "2") (pinfunction "2_2") (pintype "passive"))
      (node (ref "JA71") (pin "2") (pinfunction "2_2") (pintype "passive"))
    )
    (net (code "45") (name "/G4") (class "Default")
      (node (ref "J34") (pin "2") (pinfunction "P$2_2") (pintype "bidirectional"))
      (node (ref "JA50") (pin "2") (pinfunction "2_2") (pintype "passive"))
      (node (ref "JA51") (pin "2") (pinfunction "2_2") (pintype "passive"))
      (node (ref "JA57") (pin "2") (pinfunction "2_2") (pintype "passive"))
      (node (ref "JA64") (pin "2") (pinfunction "2_2") (pintype "passive"))
      (node (ref "JA72") (pin "2") (pinfunction "2_2") (pintype "passive"))
      (node (ref "JA78") (pin "2") (pinfunction "2_2") (pintype "passive"))
      (node (ref "JA79") (pin "2") (pinfunction "2_2") (pintype "passive"))
      (node (ref "JA87") (pin "2") (pinfunction "2_2") (pintype "passive"))
    )
    (net (code "46") (name "/G5") (class "Default")
      (node (ref "J21") (pin "2") (pinfunction "P$2_2") (pintype "bidirectional"))
      (node (ref "JA52") (pin "2") (pinfunction "2_2") (pintype "passive"))
      (node (ref "JA58") (pin "2") (pinfunction "2_2") (pintype "passive"))
      (node (ref "JA65") (pin "2") (pinfunction "2_2") (pintype "passive"))
      (node (ref "JA66") (pin "2") (pinfunction "2_2") (pintype "passive"))
      (node (ref "JA73") (pin "2") (pinfunction "2_2") (pintype "passive"))
      (node (ref "JA80") (pin "2") (pinfunction "2_2") (pintype "passive"))
      (node (ref "JA83") (pin "2") (pinfunction "2_2") (pintype "passive"))
      (node (ref "JA84") (pin "2") (pinfunction "2_2") (pintype "passive"))
    )
    (net (code "47") (name "/G6") (class "Default")
      (node (ref "J17") (pin "2") (pinfunction "P$2_2") (pintype "bidirectional"))
      (node (ref "JA59") (pin "2") (pinfunction "2_2") (pintype "passive"))
      (node (ref "JA67") (pin "2") (pinfunction "2_2") (pintype "passive"))
      (node (ref "JA67B") (pin "2") (pinfunction "2_2") (pintype "passive"))
      (node (ref "JA67B1") (pin "2") (pinfunction "2_2") (pintype "passive"))
      (node (ref "JA74B") (pin "2") (pinfunction "2_2") (pintype "passive"))
      (node (ref "JA81") (pin "2") (pinfunction "2_2") (pintype "passive"))
      (node (ref "JA85") (pin "2") (pinfunction "2_2") (pintype "passive"))
      (node (ref "JA86") (pin "2") (pinfunction "2_2") (pintype "passive"))
      (node (ref "JB74") (pin "1") (pinfunction "1_1") (pintype "passive"))
    )
    (net (code "48") (name "/GG5") (class "Default")
      (node (ref "2D2") (pin "11") (pinfunction "I_11") (pintype "input"))
      (node (ref "J19") (pin "1") (pinfunction "P$1_1") (pintype "bidirectional"))
      (node (ref "R6") (pin "2") (pinfunction "2_2") (pintype "passive"))
    )
    (net (code "49") (name "/PG3") (class "Default")
      (node (ref "2D2") (pin "3") (pinfunction "I_3") (pintype "input"))
      (node (ref "J16") (pin "1") (pinfunction "P$1_1") (pintype "bidirectional"))
      (node (ref "R4") (pin "2") (pinfunction "2_2") (pintype "passive"))
    )
    (net (code "50") (name "/PG4") (class "Default")
      (node (ref "2D2") (pin "5") (pinfunction "I_5") (pintype "input"))
      (node (ref "J34") (pin "1") (pinfunction "P$1_1") (pintype "bidirectional"))
      (node (ref "R5") (pin "2") (pinfunction "2_2") (pintype "passive"))
    )
    (net (code "51") (name "/PG6") (class "Default")
      (node (ref "2D2") (pin "13") (pinfunction "I_13") (pintype "input"))
      (node (ref "J18") (pin "1") (pinfunction "P$1_1") (pintype "bidirectional"))
      (node (ref "R7") (pin "2") (pinfunction "2_2") (pintype "passive"))
    )
    (net (code "53") (name "GND") (class "Default")
      (node (ref "2D1") (pin "4") (pinfunction "G2A_4") (pintype "input"))
      (node (ref "2D1") (pin "5") (pinfunction "G2B_5") (pintype "input"))
      (node (ref "2D1") (pin "8") (pinfunction "GND_8") (pintype "power_in"))
      (node (ref "2D2") (pin "7") (pinfunction "GND_7") (pintype "power_in"))
      (node (ref "C1") (pin "2") (pinfunction "2_2") (pintype "passive"))
      (node (ref "C2") (pin "2") (pinfunction "2_2") (pintype "passive"))
      (node (ref "SV1") (pin "1") (pinfunction "1_1") (pintype "passive"))
    )
    (net (code "54") (name "Net-(2D1A-A)") (class "Default")
      (node (ref "2D1") (pin "1") (pinfunction "A_1") (pintype "input"))
      (node (ref "J41") (pin "1") (pinfunction "P$1_1") (pintype "bidirectional"))
    )
    (net (code "55") (name "Net-(2D1A-B)") (class "Default")
      (node (ref "2D1") (pin "2") (pinfunction "B_2") (pintype "input"))
      (node (ref "J42") (pin "1") (pinfunction "P$1_1") (pintype "bidirectional"))
    )
    (net (code "56") (name "Net-(2D1A-C)") (class "Default")
      (node (ref "2D1") (pin "3") (pinfunction "C_3") (pintype "input"))
      (node (ref "J43") (pin "1") (pinfunction "P$1_1") (pintype "bidirectional"))
    )
    (net (code "57") (name "Net-(2D1A-G1)") (class "Default")
      (node (ref "2D1") (pin "6") (pinfunction "G1_6") (pintype "input"))
      (node (ref "R3") (pin "2") (pinfunction "2_2") (pintype "passive"))
    )
    (net (code "58") (name "Net-(2D1A-Y0)") (class "Default")
      (node (ref "2D1") (pin "15") (pinfunction "Y0_15") (pintype "output"))
      (node (ref "J44") (pin "2") (pinfunction "P$2_2") (pintype "bidirectional"))
    )
    (net (code "59") (name "Net-(2D1A-Y4)") (class "Default")
      (node (ref "2D1") (pin "11") (pinfunction "Y4_11") (pintype "output"))
      (node (ref "J49") (pin "2") (pinfunction "P$2_2") (pintype "bidirectional"))
    )
    (net (code "60") (name "Net-(2D1A-Y5)") (class "Default")
      (node (ref "2D1") (pin "10") (pinfunction "Y5_10") (pintype "output"))
      (node (ref "J51") (pin "2") (pinfunction "P$2_2") (pintype "bidirectional"))
    )
    (net (code "61") (name "Net-(2D1A-Y6)") (class "Default")
      (node (ref "2D1") (pin "9") (pinfunction "Y6_9") (pintype "output"))
      (node (ref "J52") (pin "2") (pinfunction "P$2_2") (pintype "bidirectional"))
    )
    (net (code "62") (name "Net-(2D1A-Y7)") (class "Default")
      (node (ref "2D1") (pin "7") (pinfunction "Y7_7") (pintype "output"))
      (node (ref "J46") (pin "2") (pinfunction "P$2_2") (pintype "bidirectional"))
    )
    (net (code "63") (name "Net-(2D2A-I)") (class "Default")
      (node (ref "2D2") (pin "1") (pinfunction "I_1") (pintype "input"))
      (node (ref "J22") (pin "1") (pinfunction "P$1_1") (pintype "bidirectional"))
    )
    (net (code "64") (name "Net-(2D2A-O)") (class "Default")
      (node (ref "2D2") (pin "2") (pinfunction "O_2") (pintype "output"))
      (node (ref "SV1") (pin "5") (pinfunction "5_5") (pintype "passive"))
    )
    (net (code "65") (name "Net-(2D2B-O)") (class "Default")
      (node (ref "2D2") (pin "4") (pinfunction "O_4") (pintype "output"))
      (node (ref "SV1") (pin "6") (pinfunction "6_6") (pintype "passive"))
    )
    (net (code "66") (name "Net-(2D2C-O)") (class "Default")
      (node (ref "2D2") (pin "6") (pinfunction "O_6") (pintype "output"))
      (node (ref "SV1") (pin "7") (pinfunction "7_7") (pintype "passive"))
    )
    (net (code "67") (name "Net-(2D2D-O)") (class "Default")
      (node (ref "2D2") (pin "8") (pinfunction "O_8") (pintype "output"))
      (node (ref "J28") (pin "2") (pinfunction "P$2_2") (pintype "bidirectional"))
    )
    (net (code "68") (name "Net-(2D2E-O)") (class "Default")
      (node (ref "2D2") (pin "10") (pinfunction "O_10") (pintype "output"))
      (node (ref "J25") (pin "2") (pinfunction "P$2_2") (pintype "bidirectional"))
    )
    (net (code "69") (name "Net-(2D2F-O)") (class "Default")
      (node (ref "2D2") (pin "12") (pinfunction "O_12") (pintype "output"))
      (node (ref "J23") (pin "2") (pinfunction "P$2_2") (pintype "bidirectional"))
    )
    (net (code "70") (name "Net-(2D2G-VCC)") (class "Default")
      (node (ref "2D2") (pin "14") (pinfunction "VCC_14") (pintype "power_in"))
      (node (ref "C2") (pin "1") (pinfunction "1_1") (pintype "passive"))
      (node (ref "D1") (pin "C") (pinfunction "C_C") (pintype "passive"))
    )
    (net (code "71") (name "Net-(D1-PadA)") (class "Default")
      (node (ref "D1") (pin "A") (pinfunction "A_A") (pintype "passive"))
      (node (ref "D2") (pin "C") (pinfunction "C_C") (pintype "passive"))
    )
    (net (code "72") (name "Net-(D47-PadA)") (class "Default")
      (node (ref "D47") (pin "A") (pinfunction "A_A") (pintype "passive"))
      (node (ref "JB47") (pin "1") (pinfunction "1_1") (pintype "passive"))
    )
    (net (code "73") (name "Net-(D48-PadA)") (class "Default")
      (node (ref "D48") (pin "A") (pinfunction "A_A") (pintype "passive"))
      (node (ref "JB48") (pin "1") (pinfunction "1_1") (pintype "passive"))
    )
    (net (code "74") (name "Net-(D49-PadA)") (class "Default")
      (node (ref "D49") (pin "A") (pinfunction "A_A") (pintype "passive"))
      (node (ref "JB49") (pin "1") (pinfunction "1_1") (pintype "passive"))
    )
    (net (code "75") (name "Net-(D50-PadA)") (class "Default")
      (node (ref "D50") (pin "A") (pinfunction "A_A") (pintype "passive"))
      (node (ref "JB50") (pin "1") (pinfunction "1_1") (pintype "passive"))
    )
    (net (code "76") (name "Net-(D51-PadA)") (class "Default")
      (node (ref "D51") (pin "A") (pinfunction "A_A") (pintype "passive"))
      (node (ref "JB51") (pin "1") (pinfunction "1_1") (pintype "passive"))
    )
    (net (code "77") (name "Net-(D52-PadA)") (class "Default")
      (node (ref "D52") (pin "A") (pinfunction "A_A") (pintype "passive"))
      (node (ref "JB52") (pin "1") (pinfunction "1_1") (pintype "passive"))
    )
    (net (code "78") (name "Net-(D53-PadA)") (class "Default")
      (node (ref "D53") (pin "A") (pinfunction "A_A") (pintype "passive"))
      (node (ref "JB53") (pin "1") (pinfunction "1_1") (pintype "passive"))
    )
    (net (code "79") (name "Net-(D54-PadA)") (class "Default")
      (node (ref "D54") (pin "A") (pinfunction "A_A") (pintype "passive"))
      (node (ref "JB54") (pin "1") (pinfunction "1_1") (pintype "passive"))
    )
    (net (code "80") (name "Net-(D55-PadA)") (class "Default")
      (node (ref "D55") (pin "A") (pinfunction "A_A") (pintype "passive"))
      (node (ref "JB55") (pin "1") (pinfunction "1_1") (pintype "passive"))
    )
    (net (code "81") (name "Net-(D56-PadA)") (class "Default")
      (node (ref "D56") (pin "A") (pinfunction "A_A") (pintype "passive"))
      (node (ref "JB56") (pin "1") (pinfunction "1_1") (pintype "passive"))
    )
    (net (code "82") (name "Net-(D57-PadA)") (class "Default")
      (node (ref "D57") (pin "A") (pinfunction "A_A") (pintype "passive"))
      (node (ref "JB57") (pin "1") (pinfunction "1_1") (pintype "passive"))
    )
    (net (code "83") (name "Net-(D58-PadA)") (class "Default")
      (node (ref "D58") (pin "A") (pinfunction "A_A") (pintype "passive"))
      (node (ref "JB58") (pin "1") (pinfunction "1_1") (pintype "passive"))
    )
    (net (code "84") (name "Net-(D59-PadA)") (class "Default")
      (node (ref "D59") (pin "A") (pinfunction "A_A") (pintype "passive"))
      (node (ref "JB59") (pin "1") (pinfunction "1_1") (pintype "passive"))
    )
    (net (code "85") (name "Net-(D60-PadA)") (class "Default")
      (node (ref "D60") (pin "A") (pinfunction "A_A") (pintype "passive"))
      (node (ref "JB60") (pin "1") (pinfunction "1_1") (pintype "passive"))
    )
    (net (code "86") (name "Net-(D61-PadA)") (class "Default")
      (node (ref "D61") (pin "A") (pinfunction "A_A") (pintype "passive"))
      (node (ref "JB61") (pin "1") (pinfunction "1_1") (pintype "passive"))
    )
    (net (code "87") (name "Net-(D62-PadA)") (class "Default")
      (node (ref "D62") (pin "A") (pinfunction "A_A") (pintype "passive"))
      (node (ref "JB62") (pin "1") (pinfunction "1_1") (pintype "passive"))
    )
    (net (code "88") (name "Net-(D63-PadA)") (class "Default")
      (node (ref "D63") (pin "A") (pinfunction "A_A") (pintype "passive"))
      (node (ref "JB63") (pin "1") (pinfunction "1_1") (pintype "passive"))
    )
    (net (code "89") (name "Net-(D64-PadA)") (class "Default")
      (node (ref "D64") (pin "A") (pinfunction "A_A") (pintype "passive"))
      (node (ref "JB64") (pin "1") (pinfunction "1_1") (pintype "passive"))
    )
    (net (code "90") (name "Net-(D64B-PadA)") (class "Default")
      (node (ref "D64B") (pin "A") (pinfunction "A_A") (pintype "passive"))
      (node (ref "JB74B") (pin "1") (pinfunction "1_1") (pintype "passive"))
    )
    (net (code "91") (name "Net-(D65-PadA)") (class "Default")
      (node (ref "D65") (pin "A") (pinfunction "A_A") (pintype "passive"))
      (node (ref "JB65") (pin "1") (pinfunction "1_1") (pintype "passive"))
    )
    (net (code "92") (name "Net-(D66-PadA)") (class "Default")
      (node (ref "D66") (pin "A") (pinfunction "A_A") (pintype "passive"))
      (node (ref "JB66") (pin "1") (pinfunction "1_1") (pintype "passive"))
    )
    (net (code "93") (name "Net-(D67-PadA)") (class "Default")
      (node (ref "D67") (pin "A") (pinfunction "A_A") (pintype "passive"))
      (node (ref "JB67") (pin "1") (pinfunction "1_1") (pintype "passive"))
    )
    (net (code "94") (name "Net-(D67B-PadA)") (class "Default")
      (node (ref "D67B") (pin "A") (pinfunction "A_A") (pintype "passive"))
      (node (ref "JB67B") (pin "1") (pinfunction "1_1") (pintype "passive"))
    )
    (net (code "95") (name "Net-(D68-PadA)") (class "Default")
      (node (ref "D68") (pin "A") (pinfunction "A_A") (pintype "passive"))
      (node (ref "JB68") (pin "1") (pinfunction "1_1") (pintype "passive"))
    )
    (net (code "96") (name "Net-(D69-PadA)") (class "Default")
      (node (ref "D69") (pin "A") (pinfunction "A_A") (pintype "passive"))
      (node (ref "JB69") (pin "1") (pinfunction "1_1") (pintype "passive"))
    )
    (net (code "97") (name "Net-(D70-PadA)") (class "Default")
      (node (ref "D70") (pin "A") (pinfunction "A_A") (pintype "passive"))
      (node (ref "JB70") (pin "1") (pinfunction "1_1") (pintype "passive"))
    )
    (net (code "98") (name "Net-(D71-PadA)") (class "Default")
      (node (ref "D71") (pin "A") (pinfunction "A_A") (pintype "passive"))
      (node (ref "JB71") (pin "1") (pinfunction "1_1") (pintype "passive"))
    )
    (net (code "99") (name "Net-(D72-PadA)") (class "Default")
      (node (ref "D72") (pin "A") (pinfunction "A_A") (pintype "passive"))
      (node (ref "JB72") (pin "1") (pinfunction "1_1") (pintype "passive"))
    )
    (net (code "100") (name "Net-(D73-PadA)") (class "Default")
      (node (ref "D73") (pin "A") (pinfunction "A_A") (pintype "passive"))
      (node (ref "JB73") (pin "1") (pinfunction "1_1") (pintype "passive"))
    )
    (net (code "101") (name "Net-(D74-PadA)") (class "Default")
      (node (ref "D74") (pin "A") (pinfunction "A_A") (pintype "passive"))
      (node (ref "JA74") (pin "2") (pinfunction "2_2") (pintype "passive"))
    )
    (net (code "102") (name "Net-(D75-PadA)") (class "Default")
      (node (ref "D75") (pin "A") (pinfunction "A_A") (pintype "passive"))
      (node (ref "JB75") (pin "1") (pinfunction "1_1") (pintype "passive"))
    )
    (net (code "103") (name "Net-(D76-PadA)") (class "Default")
      (node (ref "D76") (pin "A") (pinfunction "A_A") (pintype "passive"))
      (node (ref "JB76") (pin "1") (pinfunction "1_1") (pintype "passive"))
    )
    (net (code "104") (name "Net-(D77-PadA)") (class "Default")
      (node (ref "D77") (pin "A") (pinfunction "A_A") (pintype "passive"))
      (node (ref "JB77") (pin "1") (pinfunction "1_1") (pintype "passive"))
    )
    (net (code "105") (name "Net-(D78-PadA)") (class "Default")
      (node (ref "D78") (pin "A") (pinfunction "A_A") (pintype "passive"))
      (node (ref "JB78") (pin "1") (pinfunction "1_1") (pintype "passive"))
    )
    (net (code "106") (name "Net-(D79-PadA)") (class "Default")
      (node (ref "D79") (pin "A") (pinfunction "A_A") (pintype "passive"))
      (node (ref "JB79") (pin "1") (pinfunction "1_1") (pintype "passive"))
    )
    (net (code "107") (name "Net-(D80-PadA)") (class "Default")
      (node (ref "D80") (pin "A") (pinfunction "A_A") (pintype "passive"))
      (node (ref "JB80") (pin "1") (pinfunction "1_1") (pintype "passive"))
    )
    (net (code "108") (name "Net-(D81-PadA)") (class "Default")
      (node (ref "D81") (pin "A") (pinfunction "A_A") (pintype "passive"))
      (node (ref "JB81") (pin "1") (pinfunction "1_1") (pintype "passive"))
    )
    (net (code "109") (name "Net-(D82-PadA)") (class "Default")
      (node (ref "D82") (pin "A") (pinfunction "A_A") (pintype "passive"))
      (node (ref "JB82") (pin "1") (pinfunction "1_1") (pintype "passive"))
    )
    (net (code "110") (name "Net-(D83-PadA)") (class "Default")
      (node (ref "D83") (pin "A") (pinfunction "A_A") (pintype "passive"))
      (node (ref "JB83") (pin "1") (pinfunction "1_1") (pintype "passive"))
    )
    (net (code "111") (name "Net-(D84-PadA)") (class "Default")
      (node (ref "D84") (pin "A") (pinfunction "A_A") (pintype "passive"))
      (node (ref "JB84") (pin "1") (pinfunction "1_1") (pintype "passive"))
    )
    (net (code "112") (name "Net-(D85-PadA)") (class "Default")
      (node (ref "D85") (pin "A") (pinfunction "A_A") (pintype "passive"))
      (node (ref "JB85") (pin "1") (pinfunction "1_1") (pintype "passive"))
    )
    (net (code "113") (name "Net-(D86-PadA)") (class "Default")
      (node (ref "D86") (pin "A") (pinfunction "A_A") (pintype "passive"))
      (node (ref "JB86") (pin "1") (pinfunction "1_1") (pintype "passive"))
    )
    (net (code "114") (name "Net-(D87-PadA)") (class "Default")
      (node (ref "D87") (pin "A") (pinfunction "A_A") (pintype "passive"))
      (node (ref "JB87") (pin "1") (pinfunction "1_1") (pintype "passive"))
    )
    (net (code "115") (name "Net-(J1-P$1)") (class "Default")
      (node (ref "J1") (pin "1") (pinfunction "P$1_1") (pintype "bidirectional"))
      (node (ref "J35") (pin "2") (pinfunction "P$2_2") (pintype "bidirectional"))
    )
    (net (code "116") (name "Net-(J1-P$2)") (class "Default")
      (node (ref "J1") (pin "2") (pinfunction "P$2_2") (pintype "bidirectional"))
      (node (ref "J29") (pin "1") (pinfunction "P$1_1") (pintype "bidirectional"))
    )
    (net (code "117") (name "Net-(J2-P$1)") (class "Default")
      (node (ref "J2") (pin "1") (pinfunction "P$1_1") (pintype "bidirectional"))
      (node (ref "J7") (pin "2") (pinfunction "P$2_2") (pintype "bidirectional"))
    )
    (net (code "118") (name "Net-(J3-P$1)") (class "Default")
      (node (ref "J3") (pin "1") (pinfunction "P$1_1") (pintype "bidirectional"))
      (node (ref "J4") (pin "2") (pinfunction "P$2_2") (pintype "bidirectional"))
    )
    (net (code "119") (name "Net-(J13-P$1)") (class "Default")
      (node (ref "J13") (pin "1") (pinfunction "P$1_1") (pintype "bidirectional"))
      (node (ref "S67B") (pin "SW1") (pinfunction "PIN-1_SW1") (pintype "passive"))
      (node (ref "S67C") (pin "SW2") (pinfunction "PIN-2_SW2") (pintype "passive"))
    )
    (net (code "120") (name "Net-(J13-P$2)") (class "Default")
      (node (ref "J13") (pin "2") (pinfunction "P$2_2") (pintype "bidirectional"))
      (node (ref "JB67B") (pin "2") (pinfunction "2_2") (pintype "passive"))
    )
    (net (code "121") (name "Net-(J15-P$1)") (class "Default")
      (node (ref "J15") (pin "1") (pinfunction "P$1_1") (pintype "bidirectional"))
      (node (ref "J16") (pin "2") (pinfunction "P$2_2") (pintype "bidirectional"))
    )
    (net (code "122") (name "Net-(J17-P$1)") (class "Default")
      (node (ref "J17") (pin "1") (pinfunction "P$1_1") (pintype "bidirectional"))
      (node (ref "J18") (pin "2") (pinfunction "P$2_2") (pintype "bidirectional"))
    )
    (net (code "123") (name "Net-(J19-P$2)") (class "Default")
      (node (ref "J19") (pin "2") (pinfunction "P$2_2") (pintype "bidirectional"))
      (node (ref "J21") (pin "1") (pinfunction "P$1_1") (pintype "bidirectional"))
    )
    (net (code "124") (name "Net-(J23-P$1)") (class "Default")
      (node (ref "J23") (pin "1") (pinfunction "P$1_1") (pintype "bidirectional"))
      (node (ref "SV1") (pin "4") (pinfunction "4_4") (pintype "passive"))
    )
    (net (code "125") (name "Net-(J24-P$1)") (class "Default")
      (node (ref "J24") (pin "1") (pinfunction "P$1_1") (pintype "bidirectional"))
      (node (ref "SV1") (pin "3") (pinfunction "3_3") (pintype "passive"))
    )
    (net (code "126") (name "Net-(J24-P$2)") (class "Default")
      (node (ref "J24") (pin "2") (pinfunction "P$2_2") (pintype "bidirectional"))
      (node (ref "J25") (pin "1") (pinfunction "P$1_1") (pintype "bidirectional"))
    )
    (net (code "127") (name "Net-(J26-P$1)") (class "Default")
      (node (ref "J26") (pin "1") (pinfunction "P$1_1") (pintype "bidirectional"))
      (node (ref "SV1") (pin "2") (pinfunction "2_2") (pintype "passive"))
    )
    (net (code "128") (name "Net-(J26-P$2)") (class "Default")
      (node (ref "J26") (pin "2") (pinfunction "P$2_2") (pintype "bidirectional"))
      (node (ref "J27") (pin "1") (pinfunction "P$1_1") (pintype "bidirectional"))
    )
    (net (code "129") (name "Net-(J27-P$2)") (class "Default")
      (node (ref "J27") (pin "2") (pinfunction "P$2_2") (pintype "bidirectional"))
      (node (ref "J28") (pin "1") (pinfunction "P$1_1") (pintype "bidirectional"))
    )
    (net (code "130") (name "Net-(J30-P$1)") (class "Default")
      (node (ref "J30") (pin "1") (pinfunction "P$1_1") (pintype "bidirectional"))
      (node (ref "J32") (pin "2") (pinfunction "P$2_2") (pintype "bidirectional"))
    )
    (net (code "131") (name "Net-(J31-P$1)") (class "Default")
      (node (ref "J31") (pin "1") (pinfunction "P$1_1") (pintype "bidirectional"))
      (node (ref "J33") (pin "2") (pinfunction "P$2_2") (pintype "bidirectional"))
    )
    (net (code "132") (name "Net-(J32-P$1)") (class "Default")
      (node (ref "J32") (pin "1") (pinfunction "P$1_1") (pintype "bidirectional"))
      (node (ref "J36") (pin "2") (pinfunction "P$2_2") (pintype "bidirectional"))
    )
    (net (code "133") (name "Net-(J33-P$1)") (class "Default")
      (node (ref "J33") (pin "1") (pinfunction "P$1_1") (pintype "bidirectional"))
      (node (ref "J37") (pin "2") (pinfunction "P$2_2") (pintype "bidirectional"))
    )
    (net (code "134") (name "Net-(J35-P$1)") (class "Default")
      (node (ref "J35") (pin "1") (pinfunction "P$1_1") (pintype "bidirectional"))
      (node (ref "J39") (pin "2") (pinfunction "P$2_2") (pintype "bidirectional"))
    )
    (net (code "135") (name "Net-(J36-P$1)") (class "Default")
      (node (ref "J36") (pin "1") (pinfunction "P$1_1") (pintype "bidirectional"))
      (node (ref "J40") (pin "2") (pinfunction "P$2_2") (pintype "bidirectional"))
    )
    (net (code "136") (name "Net-(J37-P$1)") (class "Default")
      (node (ref "J37") (pin "1") (pinfunction "P$1_1") (pintype "bidirectional"))
      (node (ref "J38") (pin "2") (pinfunction "P$2_2") (pintype "bidirectional"))
    )
    (net (code "137") (name "Net-(J38-P$1)") (class "Default")
      (node (ref "J38") (pin "1") (pinfunction "P$1_1") (pintype "bidirectional"))
      (node (ref "J41") (pin "2") (pinfunction "P$2_2") (pintype "bidirectional"))
    )
    (net (code "138") (name "Net-(J39-P$1)") (class "Default")
      (node (ref "J39") (pin "1") (pinfunction "P$1_1") (pintype "bidirectional"))
      (node (ref "J43") (pin "2") (pinfunction "P$2_2") (pintype "bidirectional"))
    )
    (net (code "139") (name "Net-(J40-P$1)") (class "Default")
      (node (ref "J40") (pin "1") (pinfunction "P$1_1") (pintype "bidirectional"))
      (node (ref "J42") (pin "2") (pinfunction "P$2_2") (pintype "bidirectional"))
    )
    (net (code "140") (name "Net-(J48-P$2)") (class "Default")
      (node (ref "J48") (pin "2") (pinfunction "P$2_2") (pintype "bidirectional"))
      (node (ref "J51") (pin "1") (pinfunction "P$1_1") (pintype "bidirectional"))
    )
    (net (code "141") (name "Net-(J49-P$1)") (class "Default")
      (node (ref "J49") (pin "1") (pinfunction "P$1_1") (pintype "bidirectional"))
      (node (ref "J50") (pin "2") (pinfunction "P$2_2") (pintype "bidirectional"))
    )
    (net (code "142") (name "Net-(J52-P$1)") (class "Default")
      (node (ref "J52") (pin "1") (pinfunction "P$1_1") (pintype "bidirectional"))
      (node (ref "J53") (pin "2") (pinfunction "P$2_2") (pintype "bidirectional"))
    )
    (net (code "143") (name "Net-(S47A-PIN-1)") (class "Default")
      (node (ref "JB47") (pin "2") (pinfunction "2_2") (pintype "passive"))
      (node (ref "S47") (pin "SW1") (pinfunction "PIN-1_SW1") (pintype "passive"))
    )
    (net (code "144") (name "Net-(S47A-PIN-2)") (class "Default")
      (node (ref "JA47") (pin "1") (pinfunction "1_1") (pintype "passive"))
      (node (ref "S47") (pin "SW2") (pinfunction "PIN-2_SW2") (pintype "passive"))
    )
    (net (code "145") (name "Net-(S48A-PIN-1)") (class "Default")
      (node (ref "JB48") (pin "2") (pinfunction "2_2") (pintype "passive"))
      (node (ref "S48") (pin "SW1") (pinfunction "PIN-1_SW1") (pintype "passive"))
    )
    (net (code "146") (name "Net-(S48A-PIN-2)") (class "Default")
      (node (ref "JA48") (pin "1") (pinfunction "1_1") (pintype "passive"))
      (node (ref "S48") (pin "SW2") (pinfunction "PIN-2_SW2") (pintype "passive"))
    )
    (net (code "147") (name "Net-(S49A-PIN-1)") (class "Default")
      (node (ref "JB49") (pin "2") (pinfunction "2_2") (pintype "passive"))
      (node (ref "S49") (pin "SW1") (pinfunction "PIN-1_SW1") (pintype "passive"))
    )
    (net (code "148") (name "Net-(S49A-PIN-2)") (class "Default")
      (node (ref "JA49") (pin "1") (pinfunction "1_1") (pintype "passive"))
      (node (ref "S49") (pin "SW2") (pinfunction "PIN-2_SW2") (pintype "passive"))
    )
    (net (code "149") (name "Net-(S50A-PIN-1)") (class "Default")
      (node (ref "JA50") (pin "1") (pinfunction "1_1") (pintype "passive"))
      (node (ref "S50") (pin "SW1") (pinfunction "PIN-1_SW1") (pintype "passive"))
    )
    (net (code "150") (name "Net-(S50A-PIN-2)") (class "Default")
      (node (ref "JB50") (pin "2") (pinfunction "2_2") (pintype "passive"))
      (node (ref "S50") (pin "SW2") (pinfunction "PIN-2_SW2") (pintype "passive"))
    )
    (net (code "151") (name "Net-(S51A-PIN-1)") (class "Default")
      (node (ref "JB51") (pin "2") (pinfunction "2_2") (pintype "passive"))
      (node (ref "S51") (pin "SW1") (pinfunction "PIN-1_SW1") (pintype "passive"))
    )
    (net (code "152") (name "Net-(S51A-PIN-2)") (class "Default")
      (node (ref "JA51") (pin "1") (pinfunction "1_1") (pintype "passive"))
      (node (ref "S51") (pin "SW2") (pinfunction "PIN-2_SW2") (pintype "passive"))
    )
    (net (code "153") (name "Net-(S52A-PIN-1)") (class "Default")
      (node (ref "JB52") (pin "2") (pinfunction "2_2") (pintype "passive"))
      (node (ref "S52") (pin "SW1") (pinfunction "PIN-1_SW1") (pintype "passive"))
    )
    (net (code "154") (name "Net-(S52A-PIN-2)") (class "Default")
      (node (ref "JA52") (pin "1") (pinfunction "1_1") (pintype "passive"))
      (node (ref "S52") (pin "SW2") (pinfunction "PIN-2_SW2") (pintype "passive"))
    )
    (net (code "155") (name "Net-(S53A-PIN-1)") (class "Default")
      (node (ref "JB53") (pin "2") (pinfunction "2_2") (pintype "passive"))
      (node (ref "S53") (pin "SW1") (pinfunction "PIN-1_SW1") (pintype "passive"))
    )
    (net (code "156") (name "Net-(S53A-PIN-2)") (class "Default")
      (node (ref "JA53") (pin "1") (pinfunction "1_1") (pintype "passive"))
      (node (ref "S53") (pin "SW2") (pinfunction "PIN-2_SW2") (pintype "passive"))
    )
    (net (code "157") (name "Net-(S54A-PIN-1)") (class "Default")
      (node (ref "JB54") (pin "2") (pinfunction "2_2") (pintype "passive"))
      (node (ref "S54") (pin "SW1") (pinfunction "PIN-1_SW1") (pintype "passive"))
    )
    (net (code "158") (name "Net-(S54A-PIN-2)") (class "Default")
      (node (ref "JA54") (pin "1") (pinfunction "1_1") (pintype "passive"))
      (node (ref "S54") (pin "SW2") (pinfunction "PIN-2_SW2") (pintype "passive"))
    )
    (net (code "159") (name "Net-(S55A-PIN-1)") (class "Default")
      (node (ref "JB55") (pin "2") (pinfunction "2_2") (pintype "passive"))
      (node (ref "S55") (pin "SW1") (pinfunction "PIN-1_SW1") (pintype "passive"))
    )
    (net (code "160") (name "Net-(S55A-PIN-2)") (class "Default")
      (node (ref "JA55") (pin "1") (pinfunction "1_1") (pintype "passive"))
      (node (ref "S55") (pin "SW2") (pinfunction "PIN-2_SW2") (pintype "passive"))
    )
    (net (code "161") (name "Net-(S56A-PIN-1)") (class "Default")
      (node (ref "JB56") (pin "2") (pinfunction "2_2") (pintype "passive"))
      (node (ref "S56") (pin "SW1") (pinfunction "PIN-1_SW1") (pintype "passive"))
    )
    (net (code "162") (name "Net-(S56A-PIN-2)") (class "Default")
      (node (ref "JA56") (pin "1") (pinfunction "1_1") (pintype "passive"))
      (node (ref "S56") (pin "SW2") (pinfunction "PIN-2_SW2") (pintype "passive"))
    )
    (net (code "163") (name "Net-(S57A-PIN-1)") (class "Default")
      (node (ref "JA57") (pin "1") (pinfunction "1_1") (pintype "passive"))
      (node (ref "S57") (pin "SW1") (pinfunction "PIN-1_SW1") (pintype "passive"))
    )
    (net (code "164") (name "Net-(S57A-PIN-2)") (class "Default")
      (node (ref "JB57") (pin "2") (pinfunction "2_2") (pintype "passive"))
      (node (ref "S57") (pin "SW2") (pinfunction "PIN-2_SW2") (pintype "passive"))
    )
    (net (code "165") (name "Net-(S58A-PIN-1)") (class "Default")
      (node (ref "JA58") (pin "1") (pinfunction "1_1") (pintype "passive"))
      (node (ref "S58") (pin "SW1") (pinfunction "PIN-1_SW1") (pintype "passive"))
    )
    (net (code "166") (name "Net-(S58A-PIN-2)") (class "Default")
      (node (ref "JB58") (pin "2") (pinfunction "2_2") (pintype "passive"))
      (node (ref "S58") (pin "SW2") (pinfunction "PIN-2_SW2") (pintype "passive"))
    )
    (net (code "167") (name "Net-(S59A-PIN-1)") (class "Default")
      (node (ref "JA59") (pin "1") (pinfunction "1_1") (pintype "passive"))
      (node (ref "S59") (pin "SW1") (pinfunction "PIN-1_SW1") (pintype "passive"))
    )
    (net (code "168") (name "Net-(S59A-PIN-2)") (class "Default")
      (node (ref "JB59") (pin "2") (pinfunction "2_2") (pintype "passive"))
      (node (ref "S59") (pin "SW2") (pinfunction "PIN-2_SW2") (pintype "passive"))
    )
    (net (code "169") (name "Net-(S60A-PIN-1)") (class "Default")
      (node (ref "JB60") (pin "2") (pinfunction "2_2") (pintype "passive"))
      (node (ref "S60") (pin "SW1") (pinfunction "PIN-1_SW1") (pintype "passive"))
    )
    (net (code "170") (name "Net-(S60A-PIN-2)") (class "Default")
      (node (ref "JA60") (pin "1") (pinfunction "1_1") (pintype "passive"))
      (node (ref "S60") (pin "SW2") (pinfunction "PIN-2_SW2") (pintype "passive"))
    )
    (net (code "171") (name "Net-(S61A-PIN-1)") (class "Default")
      (node (ref "JB61") (pin "2") (pinfunction "2_2") (pintype "passive"))
      (node (ref "S61") (pin "SW1") (pinfunction "PIN-1_SW1") (pintype "passive"))
    )
    (net (code "172") (name "Net-(S61A-PIN-2)") (class "Default")
      (node (ref "JA61") (pin "1") (pinfunction "1_1") (pintype "passive"))
      (node (ref "S61") (pin "SW2") (pinfunction "PIN-2_SW2") (pintype "passive"))
    )
    (net (code "173") (name "Net-(S62A-PIN-1)") (class "Default")
      (node (ref "JA62") (pin "1") (pinfunction "1_1") (pintype "passive"))
      (node (ref "S62") (pin "SW1") (pinfunction "PIN-1_SW1") (pintype "passive"))
    )
    (net (code "174") (name "Net-(S62A-PIN-2)") (class "Default")
      (node (ref "JB62") (pin "2") (pinfunction "2_2") (pintype "passive"))
      (node (ref "S62") (pin "SW2") (pinfunction "PIN-2_SW2") (pintype "passive"))
    )
    (net (code "175") (name "Net-(S63A-PIN-1)") (class "Default")
      (node (ref "JB63") (pin "2") (pinfunction "2_2") (pintype "passive"))
      (node (ref "S63") (pin "SW1") (pinfunction "PIN-1_SW1") (pintype "passive"))
    )
    (net (code "176") (name "Net-(S63A-PIN-2)") (class "Default")
      (node (ref "JA63") (pin "1") (pinfunction "1_1") (pintype "passive"))
      (node (ref "S63") (pin "SW2") (pinfunction "PIN-2_SW2") (pintype "passive"))
    )
    (net (code "177") (name "Net-(S64A-PIN-1)") (class "Default")
      (node (ref "JA64") (pin "1") (pinfunction "1_1") (pintype "passive"))
      (node (ref "S64") (pin "SW1") (pinfunction "PIN-1_SW1") (pintype "passive"))
    )
    (net (code "178") (name "Net-(S64A-PIN-2)") (class "Default")
      (node (ref "JB64") (pin "2") (pinfunction "2_2") (pintype "passive"))
      (node (ref "S64") (pin "SW2") (pinfunction "PIN-2_SW2") (pintype "passive"))
    )
    (net (code "179") (name "Net-(S65A-PIN-1)") (class "Default")
      (node (ref "JA65") (pin "1") (pinfunction "1_1") (pintype "passive"))
      (node (ref "S65") (pin "SW1") (pinfunction "PIN-1_SW1") (pintype "passive"))
    )
    (net (code "180") (name "Net-(S65A-PIN-2)") (class "Default")
      (node (ref "JB65") (pin "2") (pinfunction "2_2") (pintype "passive"))
      (node (ref "S65") (pin "SW2") (pinfunction "PIN-2_SW2") (pintype "passive"))
    )
    (net (code "181") (name "Net-(S66A-PIN-1)") (class "Default")
      (node (ref "JB66") (pin "2") (pinfunction "2_2") (pintype "passive"))
      (node (ref "S66") (pin "SW1") (pinfunction "PIN-1_SW1") (pintype "passive"))
    )
    (net (code "182") (name "Net-(S66A-PIN-2)") (class "Default")
      (node (ref "JA66") (pin "1") (pinfunction "1_1") (pintype "passive"))
      (node (ref "S66") (pin "SW2") (pinfunction "PIN-2_SW2") (pintype "passive"))
    )
    (net (code "183") (name "Net-(S67A-PIN-1)") (class "Default")
      (node (ref "JA67") (pin "1") (pinfunction "1_1") (pintype "passive"))
      (node (ref "S67") (pin "SW1") (pinfunction "PIN-1_SW1") (pintype "passive"))
    )
    (net (code "184") (name "Net-(S67A-PIN-2)") (class "Default")
      (node (ref "JB67") (pin "2") (pinfunction "2_2") (pintype "passive"))
      (node (ref "S67") (pin "SW2") (pinfunction "PIN-2_SW2") (pintype "passive"))
    )
    (net (code "185") (name "Net-(S67B-PIN-2)") (class "Default")
      (node (ref "JA67B1") (pin "1") (pinfunction "1_1") (pintype "passive"))
      (node (ref "S67B") (pin "SW2") (pinfunction "PIN-2_SW2") (pintype "passive"))
    )
    (net (code "186") (name "Net-(S67CA-PIN-1)") (class "Default")
      (node (ref "JA67B") (pin "1") (pinfunction "1_1") (pintype "passive"))
      (node (ref "S67C") (pin "SW1") (pinfunction "PIN-1_SW1") (pintype "passive"))
    )
    (net (code "187") (name "Net-(S68A-PIN-1)") (class "Default")
      (node (ref "JB68") (pin "2") (pinfunction "2_2") (pintype "passive"))
      (node (ref "S68") (pin "SW1") (pinfunction "PIN-1_SW1") (pintype "passive"))
    )
    (net (code "188") (name "Net-(S68A-PIN-2)") (class "Default")
      (node (ref "JA68") (pin "1") (pinfunction "1_1") (pintype "passive"))
      (node (ref "S68") (pin "SW2") (pinfunction "PIN-2_SW2") (pintype "passive"))
    )
    (net (code "189") (name "Net-(S69A-PIN-1)") (class "Default")
      (node (ref "JB69") (pin "2") (pinfunction "2_2") (pintype "passive"))
      (node (ref "S69") (pin "SW1") (pinfunction "PIN-1_SW1") (pintype "passive"))
    )
    (net (code "190") (name "Net-(S69A-PIN-2)") (class "Default")
      (node (ref "JA69") (pin "1") (pinfunction "1_1") (pintype "passive"))
      (node (ref "S69") (pin "SW2") (pinfunction "PIN-2_SW2") (pintype "passive"))
    )
    (net (code "191") (name "Net-(S70A-PIN-1)") (class "Default")
      (node (ref "JB70") (pin "2") (pinfunction "2_2") (pintype "passive"))
      (node (ref "S70") (pin "SW1") (pinfunction "PIN-1_SW1") (pintype "passive"))
    )
    (net (code "192") (name "Net-(S70A-PIN-2)") (class "Default")
      (node (ref "JA70") (pin "1") (pinfunction "1_1") (pintype "passive"))
      (node (ref "S70") (pin "SW2") (pinfunction "PIN-2_SW2") (pintype "passive"))
    )
    (net (code "193") (name "Net-(S71A-PIN-1)") (class "Default")
      (node (ref "JB71") (pin "2") (pinfunction "2_2") (pintype "passive"))
      (node (ref "S71") (pin "SW1") (pinfunction "PIN-1_SW1") (pintype "passive"))
    )
    (net (code "194") (name "Net-(S71A-PIN-2)") (class "Default")
      (node (ref "JA71") (pin "1") (pinfunction "1_1") (pintype "passive"))
      (node (ref "S71") (pin "SW2") (pinfunction "PIN-2_SW2") (pintype "passive"))
    )
    (net (code "195") (name "Net-(S72A-PIN-1)") (class "Default")
      (node (ref "JA72") (pin "1") (pinfunction "1_1") (pintype "passive"))
      (node (ref "S72") (pin "SW1") (pinfunction "PIN-1_SW1") (pintype "passive"))
    )
    (net (code "196") (name "Net-(S72A-PIN-2)") (class "Default")
      (node (ref "JB72") (pin "2") (pinfunction "2_2") (pintype "passive"))
      (node (ref "S72") (pin "SW2") (pinfunction "PIN-2_SW2") (pintype "passive"))
    )
    (net (code "197") (name "Net-(S73A-PIN-1)") (class "Default")
      (node (ref "JA73") (pin "1") (pinfunction "1_1") (pintype "passive"))
      (node (ref "S73") (pin "SW1") (pinfunction "PIN-1_SW1") (pintype "passive"))
    )
    (net (code "198") (name "Net-(S73A-PIN-2)") (class "Default")
      (node (ref "JB73") (pin "2") (pinfunction "2_2") (pintype "passive"))
      (node (ref "S73") (pin "SW2") (pinfunction "PIN-2_SW2") (pintype "passive"))
    )
    (net (code "199") (name "Net-(S74A-PIN-1)") (class "Default")
      (node (ref "JA74B") (pin "1") (pinfunction "1_1") (pintype "passive"))
      (node (ref "S74") (pin "SW1") (pinfunction "PIN-1_SW1") (pintype "passive"))
    )
    (net (code "200") (name "Net-(S74A-PIN-2)") (class "Default")
      (node (ref "JB74B") (pin "2") (pinfunction "2_2") (pintype "passive"))
      (node (ref "S74") (pin "SW2") (pinfunction "PIN-2_SW2") (pintype "passive"))
    )
    (net (code "201") (name "Net-(S74AA-PIN-1)") (class "Default")
      (node (ref "JB74") (pin "2") (pinfunction "2_2") (pintype "passive"))
      (node (ref "S74A") (pin "SW1") (pinfunction "PIN-1_SW1") (pintype "passive"))
    )
    (net (code "202") (name "Net-(S74AA-PIN-2)") (class "Default")
      (node (ref "JA74") (pin "1") (pinfunction "1_1") (pintype "passive"))
      (node (ref "S74A") (pin "SW2") (pinfunction "PIN-2_SW2") (pintype "passive"))
    )
    (net (code "203") (name "Net-(S75A-PIN-1)") (class "Default")
      (node (ref "JB75") (pin "2") (pinfunction "2_2") (pintype "passive"))
      (node (ref "S75") (pin "SW1") (pinfunction "PIN-1_SW1") (pintype "passive"))
    )
    (net (code "204") (name "Net-(S75A-PIN-2)") (class "Default")
      (node (ref "JA75") (pin "1") (pinfunction "1_1") (pintype "passive"))
      (node (ref "S75") (pin "SW2") (pinfunction "PIN-2_SW2") (pintype "passive"))
    )
    (net (code "205") (name "Net-(S76A-PIN-1)") (class "Default")
      (node (ref "JA76") (pin "1") (pinfunction "1_1") (pintype "passive"))
      (node (ref "S76") (pin "SW1") (pinfunction "PIN-1_SW1") (pintype "passive"))
    )
    (net (code "206") (name "Net-(S76A-PIN-2)") (class "Default")
      (node (ref "JB76") (pin "2") (pinfunction "2_2") (pintype "passive"))
      (node (ref "S76") (pin "SW2") (pinfunction "PIN-2_SW2") (pintype "passive"))
    )
    (net (code "207") (name "Net-(S77A-PIN-1)") (class "Default")
      (node (ref "JB77") (pin "2") (pinfunction "2_2") (pintype "passive"))
      (node (ref "S77") (pin "SW1") (pinfunction "PIN-1_SW1") (pintype "passive"))
    )
    (net (code "208") (name "Net-(S77A-PIN-2)") (class "Default")
      (node (ref "JA77") (pin "1") (pinfunction "1_1") (pintype "passive"))
      (node (ref "S77") (pin "SW2") (pinfunction "PIN-2_SW2") (pintype "passive"))
    )
    (net (code "209") (name "Net-(S78A-PIN-1)") (class "Default")
      (node (ref "JA78") (pin "1") (pinfunction "1_1") (pintype "passive"))
      (node (ref "S78") (pin "SW1") (pinfunction "PIN-1_SW1") (pintype "passive"))
    )
    (net (code "210") (name "Net-(S78A-PIN-2)") (class "Default")
      (node (ref "JB78") (pin "2") (pinfunction "2_2") (pintype "passive"))
      (node (ref "S78") (pin "SW2") (pinfunction "PIN-2_SW2") (pintype "passive"))
    )
    (net (code "211") (name "Net-(S79A-PIN-1)") (class "Default")
      (node (ref "JA79") (pin "1") (pinfunction "1_1") (pintype "passive"))
      (node (ref "S79") (pin "SW1") (pinfunction "PIN-1_SW1") (pintype "passive"))
    )
    (net (code "212") (name "Net-(S79A-PIN-2)") (class "Default")
      (node (ref "JB79") (pin "2") (pinfunction "2_2") (pintype "passive"))
      (node (ref "S79") (pin "SW2") (pinfunction "PIN-2_SW2") (pintype "passive"))
    )
    (net (code "213") (name "Net-(S80A-PIN-1)") (class "Default")
      (node (ref "JA80") (pin "1") (pinfunction "1_1") (pintype "passive"))
      (node (ref "S80") (pin "SW1") (pinfunction "PIN-1_SW1") (pintype "passive"))
    )
    (net (code "214") (name "Net-(S80A-PIN-2)") (class "Default")
      (node (ref "JB80") (pin "2") (pinfunction "2_2") (pintype "passive"))
      (node (ref "S80") (pin "SW2") (pinfunction "PIN-2_SW2") (pintype "passive"))
    )
    (net (code "215") (name "Net-(S81A-PIN-1)") (class "Default")
      (node (ref "JA81") (pin "1") (pinfunction "1_1") (pintype "passive"))
      (node (ref "S81") (pin "SW1") (pinfunction "PIN-1_SW1") (pintype "passive"))
      (node (ref "S81A") (pin "SW1") (pinfunction "PIN-1_SW1") (pintype "passive"))
    )
    (net (code "216") (name "Net-(S81A-PIN-2)") (class "Default")
      (node (ref "JB81") (pin "2") (pinfunction "2_2") (pintype "passive"))
      (node (ref "S81") (pin "SW2") (pinfunction "PIN-2_SW2") (pintype "passive"))
      (node (ref "S81A") (pin "SW2") (pinfunction "PIN-2_SW2") (pintype "passive"))
    )
    (net (code "217") (name "Net-(S82A-PIN-1)") (class "Default")
      (node (ref "JB82") (pin "2") (pinfunction "2_2") (pintype "passive"))
      (node (ref "S82") (pin "SW1") (pinfunction "PIN-1_SW1") (pintype "passive"))
    )
    (net (code "218") (name "Net-(S82A-PIN-2)") (class "Default")
      (node (ref "JA82") (pin "1") (pinfunction "1_1") (pintype "passive"))
      (node (ref "S82") (pin "SW2") (pinfunction "PIN-2_SW2") (pintype "passive"))
    )
    (net (code "219") (name "Net-(S83A-PIN-1)") (class "Default")
      (node (ref "JA83") (pin "1") (pinfunction "1_1") (pintype "passive"))
      (node (ref "S83") (pin "SW1") (pinfunction "PIN-1_SW1") (pintype "passive"))
    )
    (net (code "220") (name "Net-(S83A-PIN-2)") (class "Default")
      (node (ref "JB83") (pin "2") (pinfunction "2_2") (pintype "passive"))
      (node (ref "S83") (pin "SW2") (pinfunction "PIN-2_SW2") (pintype "passive"))
    )
    (net (code "221") (name "Net-(S84A-PIN-1)") (class "Default")
      (node (ref "JA84") (pin "1") (pinfunction "1_1") (pintype "passive"))
      (node (ref "S84") (pin "SW1") (pinfunction "PIN-1_SW1") (pintype "passive"))
    )
    (net (code "222") (name "Net-(S84A-PIN-2)") (class "Default")
      (node (ref "JB84") (pin "2") (pinfunction "2_2") (pintype "passive"))
      (node (ref "S84") (pin "SW2") (pinfunction "PIN-2_SW2") (pintype "passive"))
    )
    (net (code "223") (name "Net-(S85A-PIN-1)") (class "Default")
      (node (ref "JA85") (pin "1") (pinfunction "1_1") (pintype "passive"))
      (node (ref "S85") (pin "SW1") (pinfunction "PIN-1_SW1") (pintype "passive"))
    )
    (net (code "224") (name "Net-(S85A-PIN-2)") (class "Default")
      (node (ref "JB85") (pin "2") (pinfunction "2_2") (pintype "passive"))
      (node (ref "S85") (pin "SW2") (pinfunction "PIN-2_SW2") (pintype "passive"))
    )
    (net (code "225") (name "Net-(S86A-PIN-1)") (class "Default")
      (node (ref "JB86") (pin "2") (pinfunction "2_2") (pintype "passive"))
      (node (ref "S86") (pin "SW1") (pinfunction "PIN-1_SW1") (pintype "passive"))
    )
    (net (code "226") (name "Net-(S86A-PIN-2)") (class "Default")
      (node (ref "JA86") (pin "1") (pinfunction "1_1") (pintype "passive"))
      (node (ref "S86") (pin "SW2") (pinfunction "PIN-2_SW2") (pintype "passive"))
    )
    (net (code "227") (name "Net-(S87A-PIN-1)") (class "Default")
      (node (ref "JA87") (pin "1") (pinfunction "1_1") (pintype "passive"))
      (node (ref "S87") (pin "SW1") (pinfunction "PIN-1_SW1") (pintype "passive"))
    )
    (net (code "228") (name "Net-(S87A-PIN-2)") (class "Default")
      (node (ref "JB87") (pin "2") (pinfunction "2_2") (pintype "passive"))
      (node (ref "S87") (pin "SW2") (pinfunction "PIN-2_SW2") (pintype "passive"))
    )
  )
)
